# Blueberry_Pi.net
KiCad netlist of a schematic drawn in EAGLE
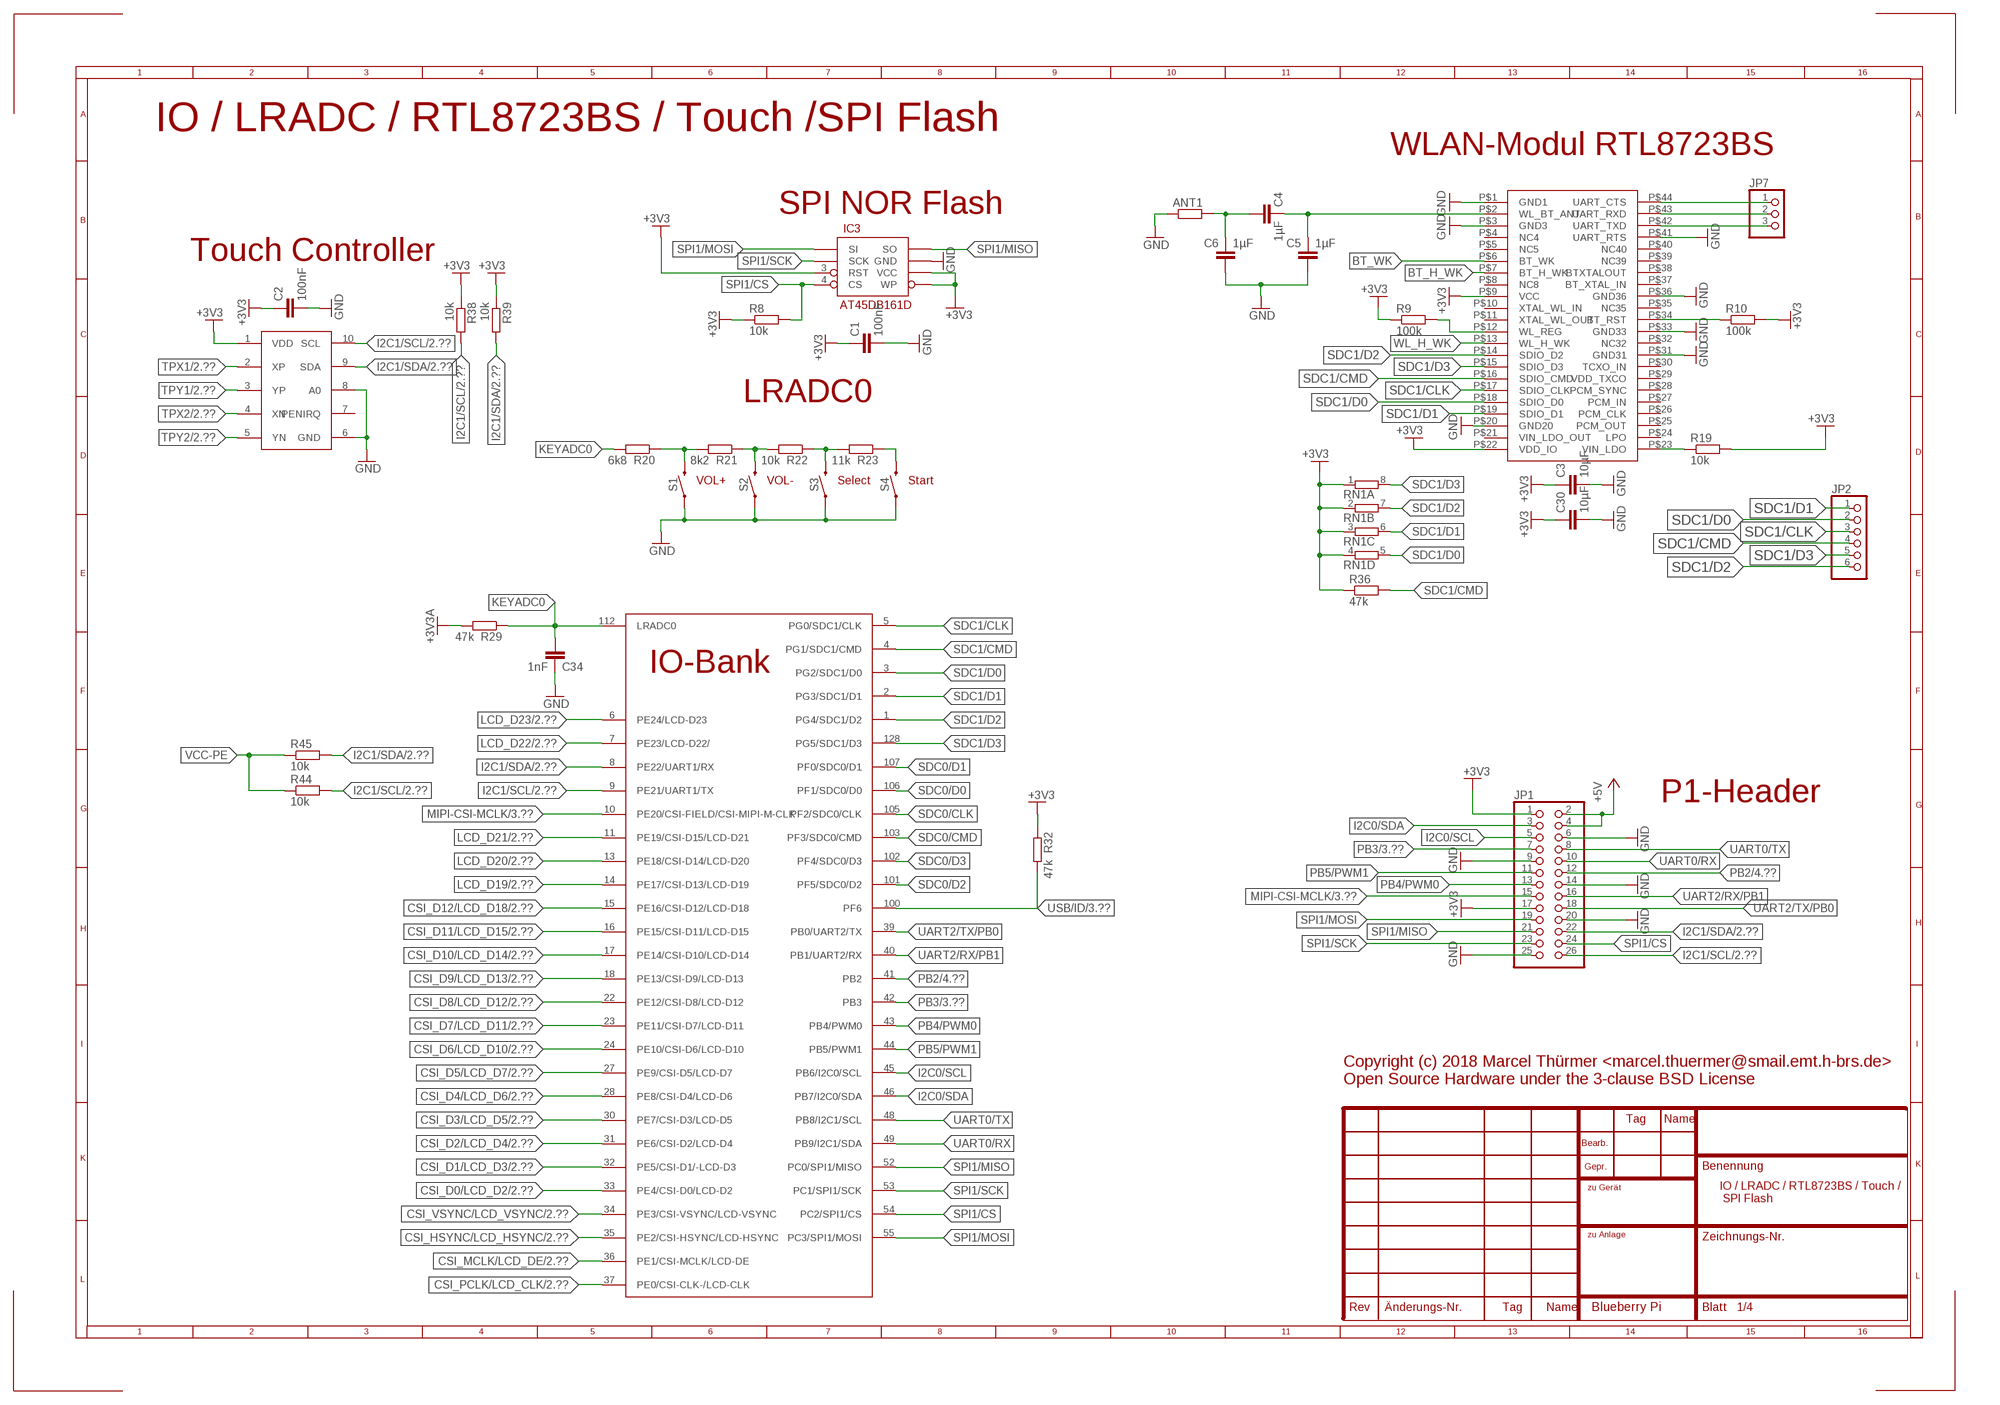
[diagram p0: schematic, sheet 1]
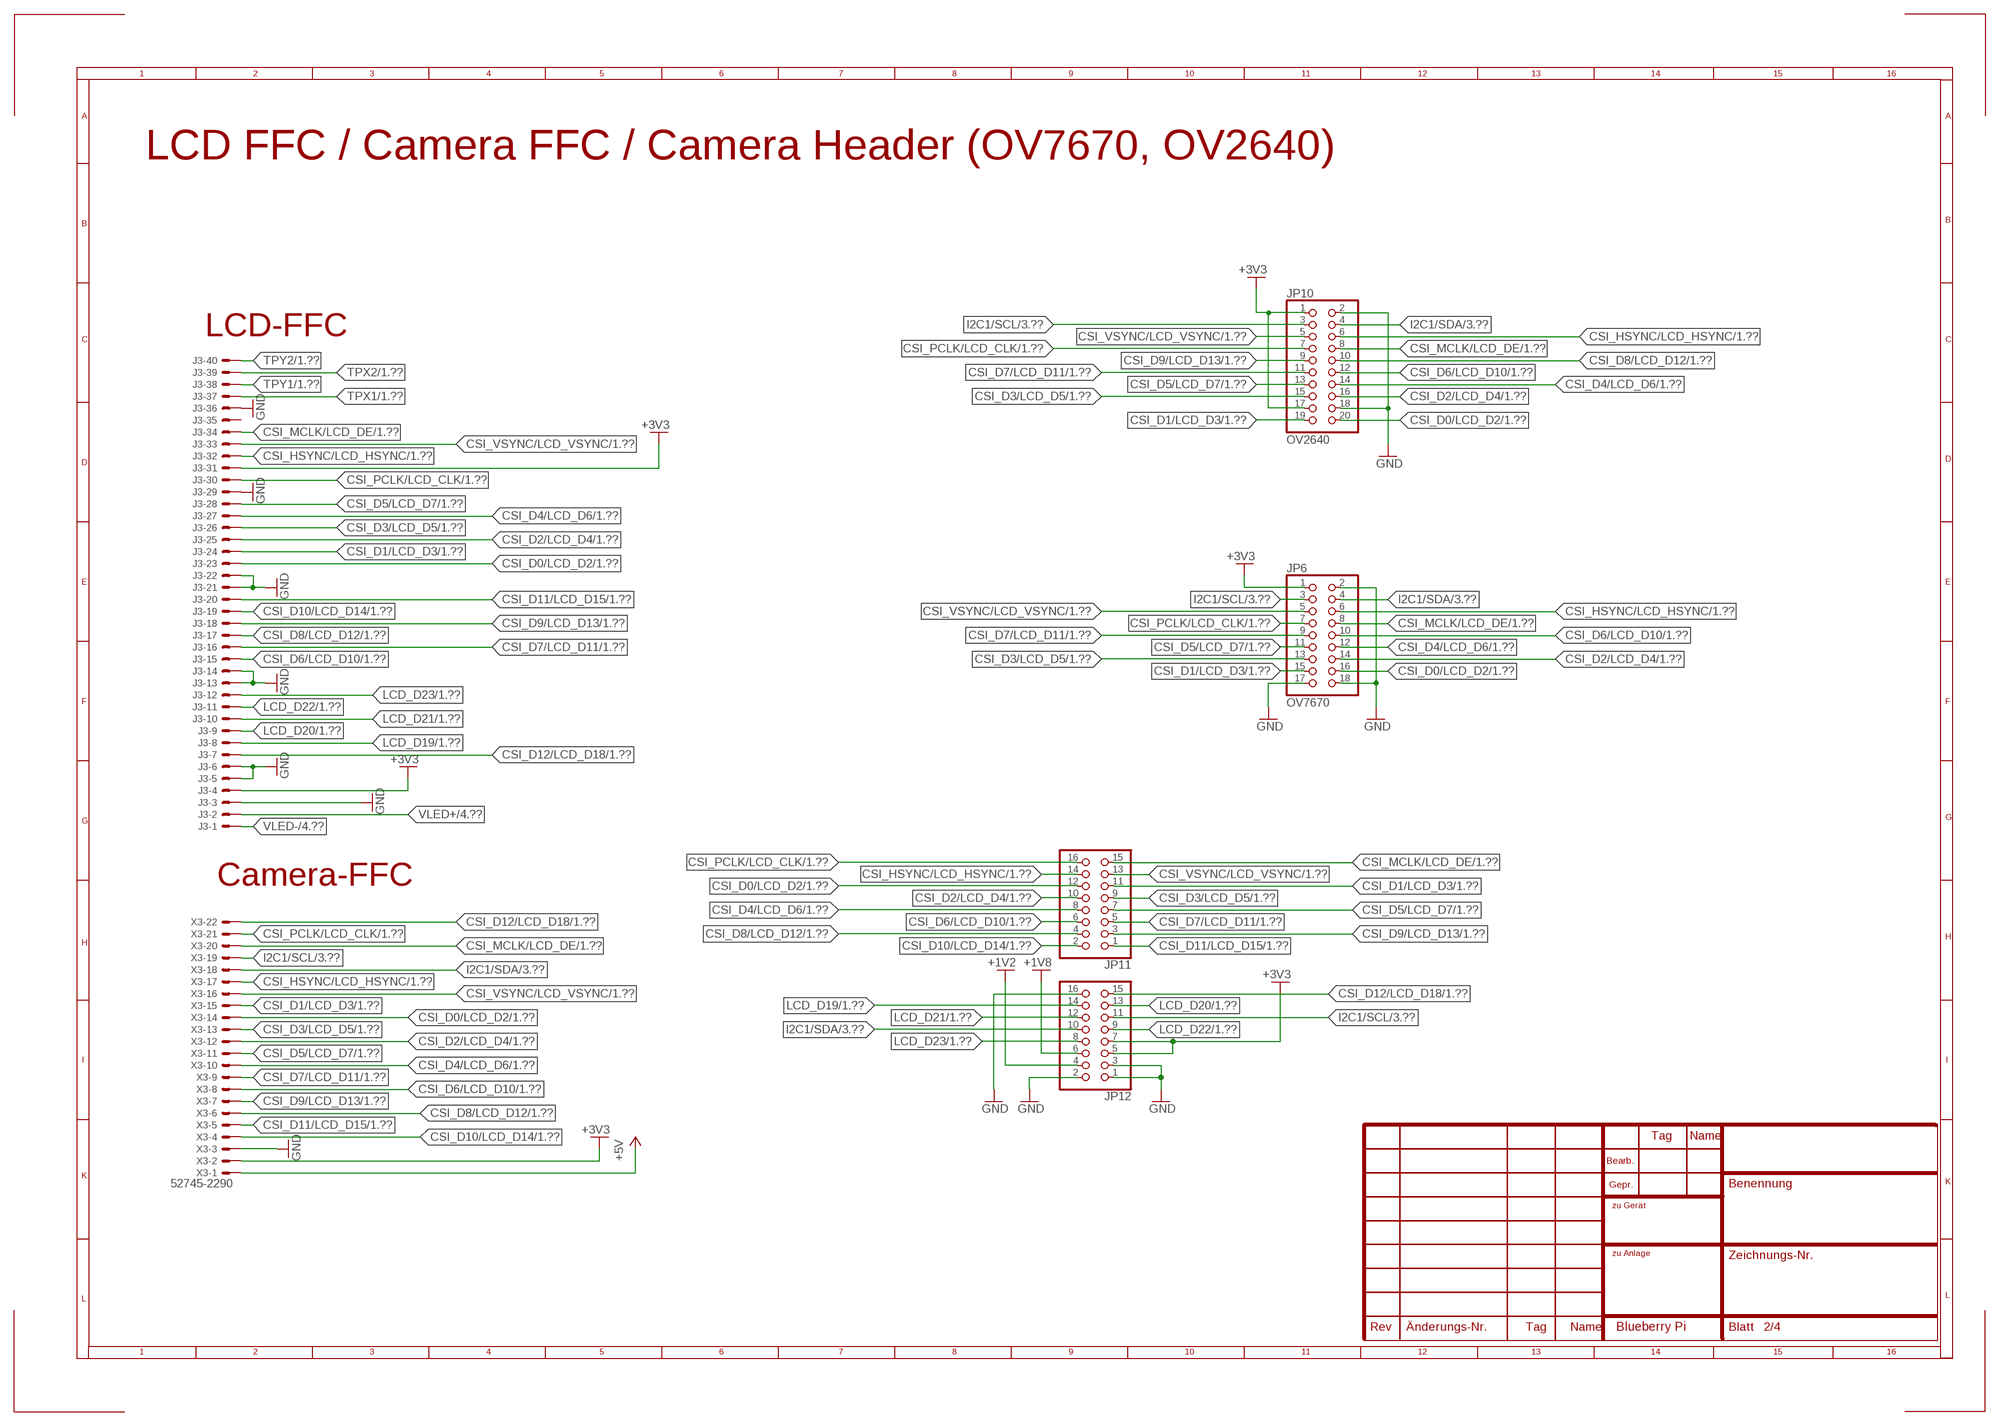
[diagram p1: schematic, sheet 2]
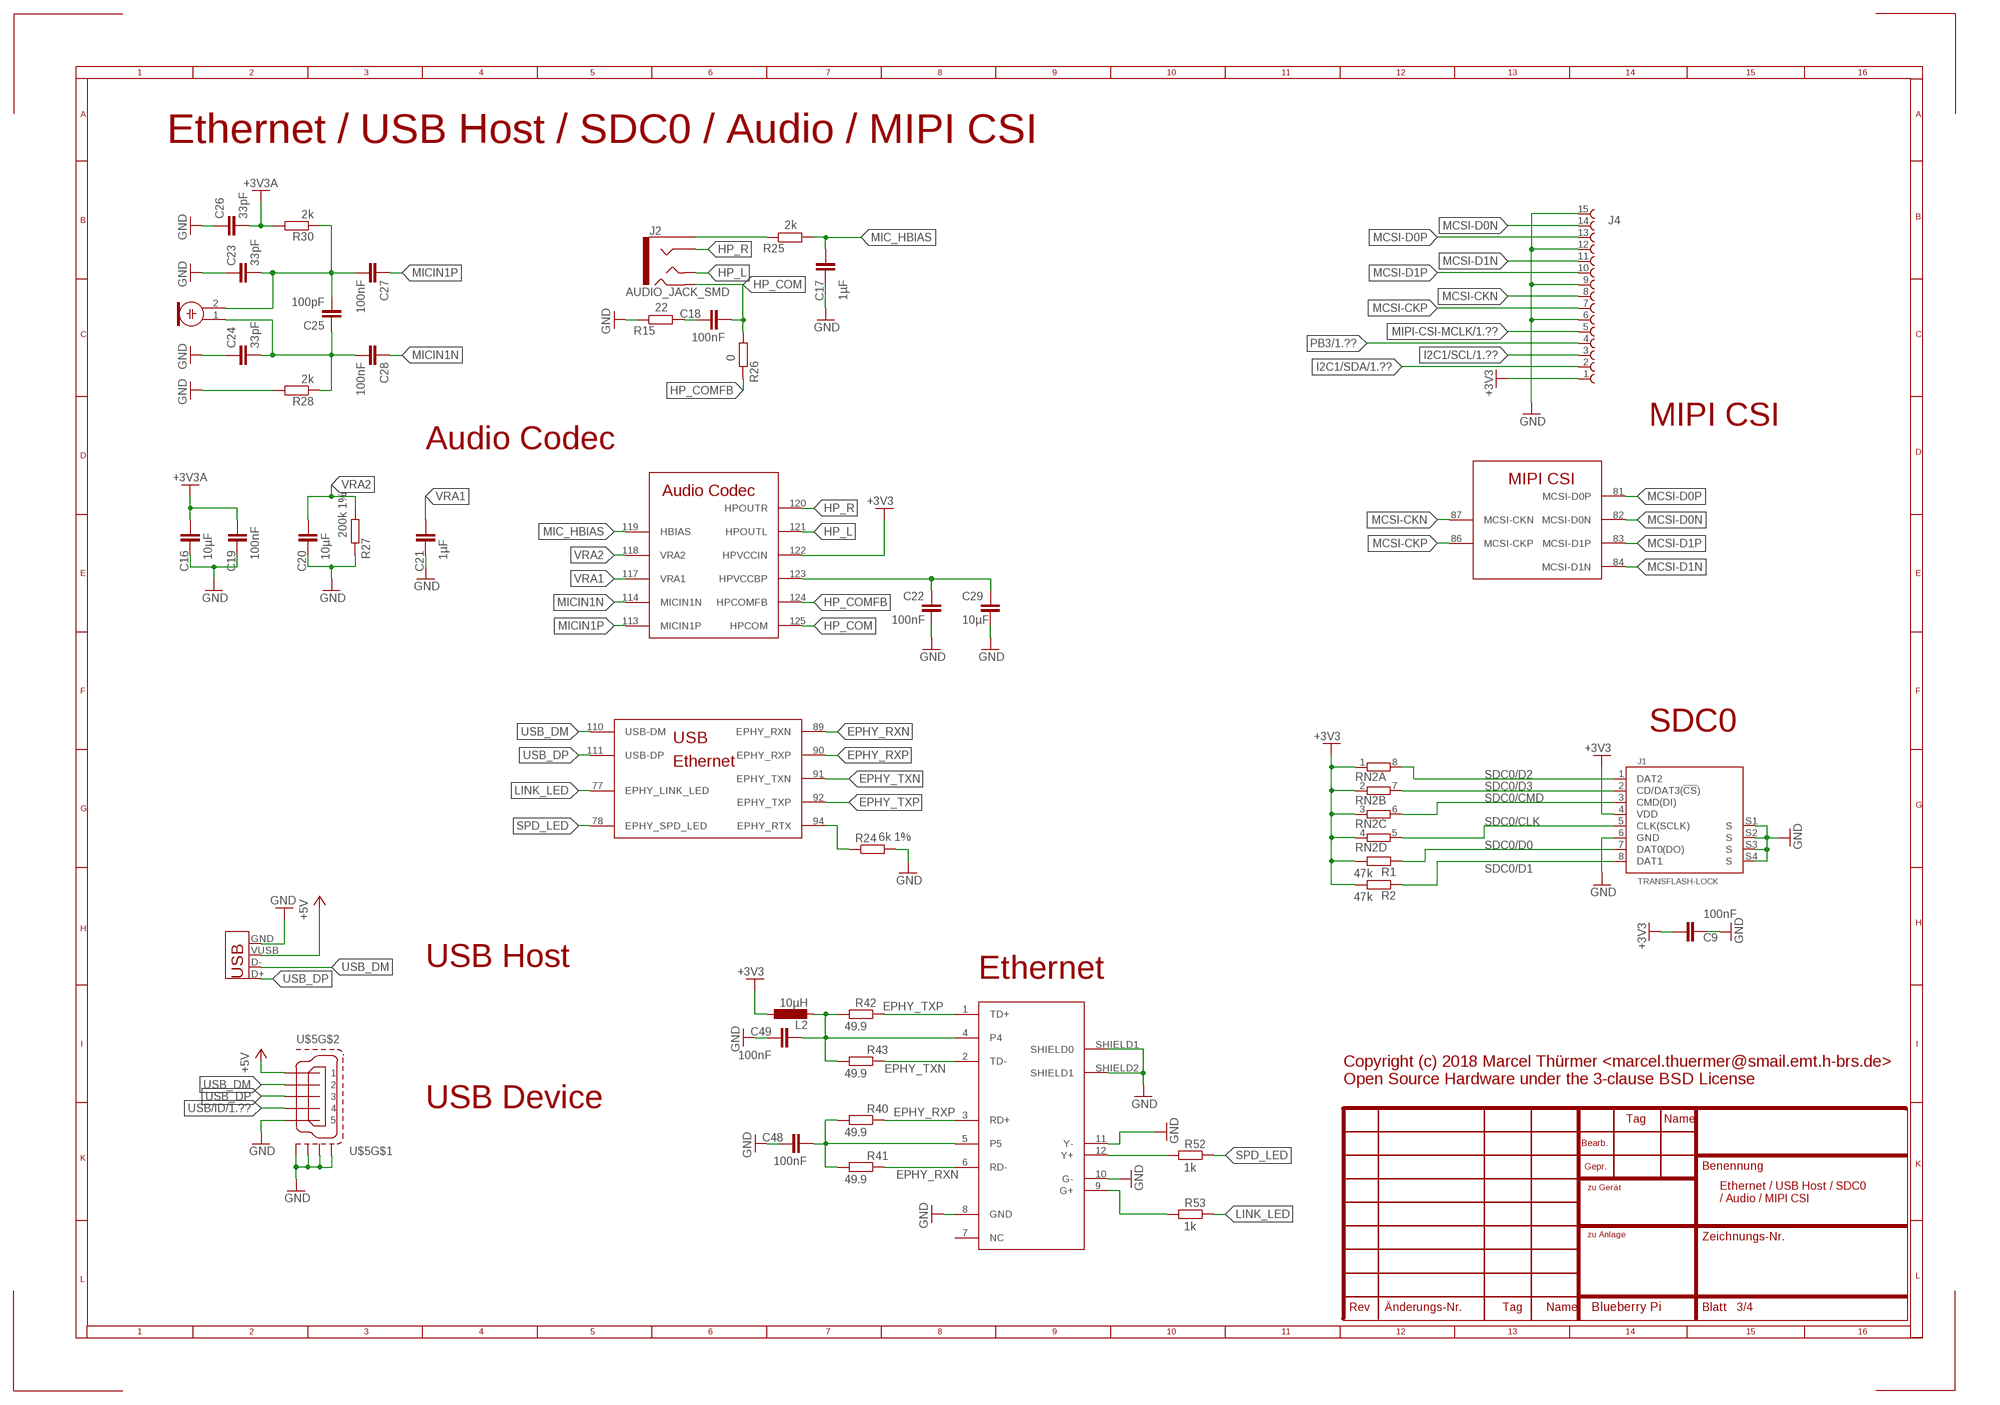
[diagram p2: schematic, sheet 3]
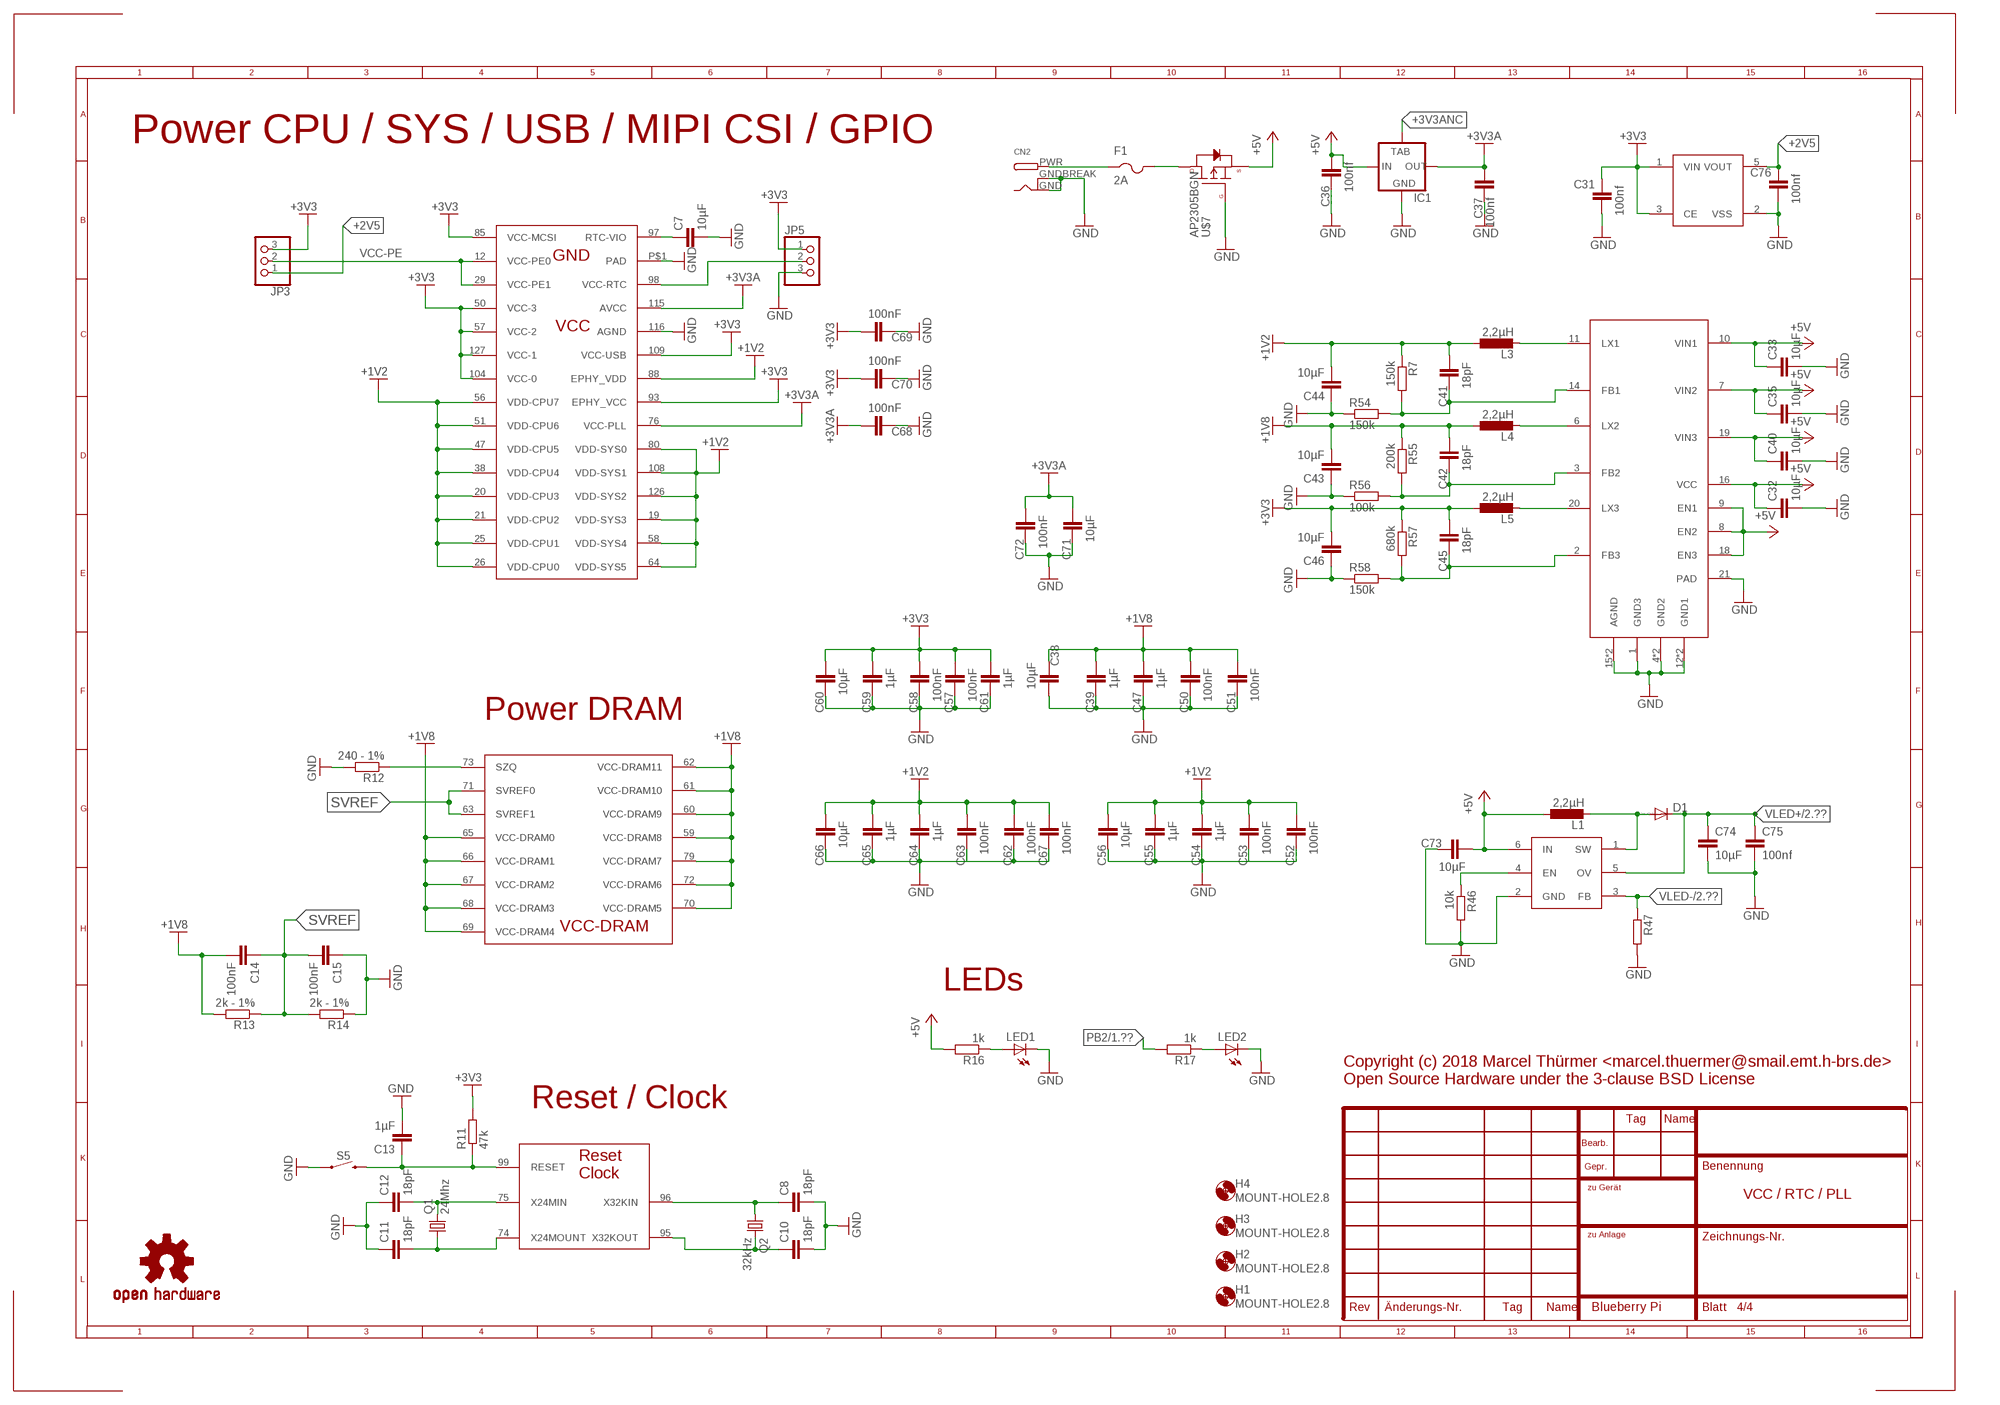
[diagram p3: schematic, sheet 4]

(export (version "E")
  (design (tool "Eeschema 10.0.6"))
  (components
    (comp (ref "J3")
      (value "40PINFPCH15-1LW")
      (footprint "eagle-import:XF2H-4015-1LW")
      (libsource (lib "eagle-import") (part "40PINFPC15-1LWH"))
    )
    (comp (ref "JP6")
      (value "OV7670")
      (footprint "eagle-import:2X09")
      (libsource (lib "eagle-import") (part "PINHD-2X9"))
    )
    (comp (ref "JP10")
      (value "OV2640")
      (footprint "eagle-import:2X10")
      (libsource (lib "eagle-import") (part "PINHD-2X10"))
    )
    (comp (ref "JP11")
      (value "PINHD-2X8M")
      (footprint "eagle-import:2X08M")
      (libsource (lib "eagle-import") (part "PINHD-2X8M"))
    )
    (comp (ref "JP12")
      (value "PINHD-2X8M")
      (footprint "eagle-import:2X08M")
      (libsource (lib "eagle-import") (part "PINHD-2X8M"))
    )
    (comp (ref "X3")
      (value "52745-2290")
      (footprint "eagle-import:52745-2290")
      (libsource (lib "eagle-import") (part "52745-2290"))
    )
    (comp (ref "ANT1")
      (value "R-EU_R1206")
      (footprint "eagle-import:R1206")
      (libsource (lib "eagle-import") (part "R-EU_R1206"))
    )
    (comp (ref "C1")
      (value "100nF")
      (footprint "eagle-import:C0603")
      (libsource (lib "eagle-import") (part "C-EUC0603"))
    )
    (comp (ref "C2")
      (value "100nF")
      (footprint "eagle-import:C0603")
      (libsource (lib "eagle-import") (part "C-EUC0603"))
    )
    (comp (ref "C3")
      (value "10µF")
      (footprint "eagle-import:C0805")
      (libsource (lib "eagle-import") (part "C-EUC0805"))
    )
    (comp (ref "C4")
      (value "1µF")
      (footprint "eagle-import:C0603")
      (libsource (lib "eagle-import") (part "C-EUC0603"))
    )
    (comp (ref "C5")
      (value "1µF")
      (footprint "eagle-import:C0603")
      (libsource (lib "eagle-import") (part "C-EUC0603"))
    )
    (comp (ref "C6")
      (value "1µF")
      (footprint "eagle-import:C0603")
      (libsource (lib "eagle-import") (part "C-EUC0603"))
    )
    (comp (ref "C30")
      (value "10µF")
      (footprint "eagle-import:C0805")
      (libsource (lib "eagle-import") (part "C-EUC0805"))
    )
    (comp (ref "C34")
      (value "1nF")
      (footprint "eagle-import:C0603")
      (libsource (lib "eagle-import") (part "C-EUC0603"))
    )
    (comp (ref "IC3")
      (value "AT45DB161D")
      (footprint "eagle-import:SO08-EIAJ")
      (libsource (lib "eagle-import") (part "AT45DB161D"))
    )
    (comp (ref "JP1")
      (value "PINHD-2X13")
      (footprint "eagle-import:2X13")
      (libsource (lib "eagle-import") (part "PINHD-2X13"))
    )
    (comp (ref "JP2")
      (value "PINHD-1X6_2.00")
      (footprint "eagle-import:1X06M")
      (libsource (lib "eagle-import") (part "PINHD-1X6_2.00"))
    )
    (comp (ref "JP7")
      (value "PINHD-1X3M")
      (footprint "eagle-import:1X03M")
      (libsource (lib "eagle-import") (part "PINHD-1X3M"))
    )
    (comp (ref "R8")
      (value "10k")
      (footprint "eagle-import:R0603")
      (libsource (lib "eagle-import") (part "R-EU_R0603"))
    )
    (comp (ref "R9")
      (value "100k")
      (footprint "eagle-import:R0603")
      (libsource (lib "eagle-import") (part "R-EU_R0603"))
    )
    (comp (ref "R10")
      (value "100k")
      (footprint "eagle-import:R0603")
      (libsource (lib "eagle-import") (part "R-EU_R0603"))
    )
    (comp (ref "R19")
      (value "10k")
      (footprint "eagle-import:R0603")
      (libsource (lib "eagle-import") (part "R-EU_R0603"))
    )
    (comp (ref "R20")
      (value "6k8")
      (footprint "eagle-import:R0603")
      (libsource (lib "eagle-import") (part "R-EU_R0603"))
    )
    (comp (ref "R21")
      (value "8k2")
      (footprint "eagle-import:R0603")
      (libsource (lib "eagle-import") (part "R-EU_R0603"))
    )
    (comp (ref "R22")
      (value "10k")
      (footprint "eagle-import:R0603")
      (libsource (lib "eagle-import") (part "R-EU_R0603"))
    )
    (comp (ref "R23")
      (value "11k")
      (footprint "eagle-import:R0603")
      (libsource (lib "eagle-import") (part "R-EU_R0603"))
    )
    (comp (ref "R29")
      (value "47k")
      (footprint "eagle-import:R0603")
      (libsource (lib "eagle-import") (part "R-EU_R0603"))
    )
    (comp (ref "R32")
      (value "47k")
      (footprint "eagle-import:R0603")
      (libsource (lib "eagle-import") (part "R-EU_R0603"))
    )
    (comp (ref "R36")
      (value "47k")
      (footprint "eagle-import:R0603")
      (libsource (lib "eagle-import") (part "R-EU_R0603"))
    )
    (comp (ref "R38")
      (value "10k")
      (footprint "eagle-import:R0603")
      (libsource (lib "eagle-import") (part "R-EU_R0603"))
    )
    (comp (ref "R39")
      (value "10k")
      (footprint "eagle-import:R0603")
      (libsource (lib "eagle-import") (part "R-EU_R0603"))
    )
    (comp (ref "R44")
      (value "10k")
      (footprint "eagle-import:R0603")
      (libsource (lib "eagle-import") (part "R-EU_R0603"))
    )
    (comp (ref "R45")
      (value "10k")
      (footprint "eagle-import:R0603")
      (libsource (lib "eagle-import") (part "R-EU_R0603"))
    )
    (comp (ref "RN1")
      (value "4R-NEXB38V")
      (footprint "eagle-import:EXB38V")
      (libsource (lib "eagle-import") (part "4R-NEXB38V"))
    )
    (comp (ref "S1")
      (value "MOMENTARY-SWITCH-SPST-SMD-6.0X3.5MM")
      (footprint "eagle-import:TACTILE_SWITCH_SMD_6.0X3.5MM")
      (libsource (lib "eagle-import") (part "MOMENTARY-SWITCH-SPST-SMD-6.0X3.5MM"))
    )
    (comp (ref "S2")
      (value "MOMENTARY-SWITCH-SPST-SMD-6.0X3.5MM")
      (footprint "eagle-import:TACTILE_SWITCH_SMD_6.0X3.5MM")
      (libsource (lib "eagle-import") (part "MOMENTARY-SWITCH-SPST-SMD-6.0X3.5MM"))
    )
    (comp (ref "S3")
      (value "MOMENTARY-SWITCH-SPST-SMD-6.0X3.5MM")
      (footprint "eagle-import:TACTILE_SWITCH_SMD_6.0X3.5MM")
      (libsource (lib "eagle-import") (part "MOMENTARY-SWITCH-SPST-SMD-6.0X3.5MM"))
    )
    (comp (ref "S4")
      (value "MOMENTARY-SWITCH-SPST-SMD-6.0X3.5MM")
      (footprint "eagle-import:TACTILE_SWITCH_SMD_6.0X3.5MM")
      (libsource (lib "eagle-import") (part "MOMENTARY-SWITCH-SPST-SMD-6.0X3.5MM"))
    )
    (comp (ref "U$1")
      (value "V3S")
      (footprint "eagle-import:QFP-128")
      (libsource (lib "eagle-import") (part "V3S"))
    )
    (comp (ref "U$2")
      (value "RTL8723BS")
      (footprint "eagle-import:LGA")
      (libsource (lib "eagle-import") (part "RTL8723BS"))
    )
    (comp (ref "U$8")
      (value "NS2009")
      (footprint "eagle-import:MSOP10")
      (libsource (lib "eagle-import") (part "NS2009"))
    )
    (comp (ref "C7")
      (value "10µF")
      (footprint "eagle-import:C0805")
      (libsource (lib "eagle-import") (part "C-EUC0805"))
    )
    (comp (ref "C8")
      (value "18pF")
      (footprint "eagle-import:C0603")
      (libsource (lib "eagle-import") (part "C-EUC0603"))
    )
    (comp (ref "C10")
      (value "18pF")
      (footprint "eagle-import:C0603")
      (libsource (lib "eagle-import") (part "C-EUC0603"))
    )
    (comp (ref "C11")
      (value "18pF")
      (footprint "eagle-import:C0603")
      (libsource (lib "eagle-import") (part "C-EUC0603"))
    )
    (comp (ref "C12")
      (value "18pF")
      (footprint "eagle-import:C0603")
      (libsource (lib "eagle-import") (part "C-EUC0603"))
    )
    (comp (ref "C13")
      (value "1µF")
      (footprint "eagle-import:C0603")
      (libsource (lib "eagle-import") (part "C-EUC0603"))
    )
    (comp (ref "C14")
      (value "100nF")
      (footprint "eagle-import:C0603")
      (libsource (lib "eagle-import") (part "C-EUC0603"))
    )
    (comp (ref "C15")
      (value "100nF")
      (footprint "eagle-import:C0603")
      (libsource (lib "eagle-import") (part "C-EUC0603"))
    )
    (comp (ref "C31")
      (value "100nf")
      (footprint "eagle-import:C0603")
      (libsource (lib "eagle-import") (part "C-EUC0603"))
    )
    (comp (ref "C32")
      (value "10µF")
      (footprint "eagle-import:C0805")
      (libsource (lib "eagle-import") (part "rcl_334_C-EUC0805"))
    )
    (comp (ref "C33")
      (value "10µF")
      (footprint "eagle-import:C0805")
      (libsource (lib "eagle-import") (part "rcl_334_C-EUC0805"))
    )
    (comp (ref "C35")
      (value "10µF")
      (footprint "eagle-import:C0805")
      (libsource (lib "eagle-import") (part "rcl_334_C-EUC0805"))
    )
    (comp (ref "C36")
      (value "100nf")
      (footprint "eagle-import:C0603")
      (libsource (lib "eagle-import") (part "C-EUC0603"))
    )
    (comp (ref "C37")
      (value "100nf")
      (footprint "eagle-import:C0603")
      (libsource (lib "eagle-import") (part "C-EUC0603"))
    )
    (comp (ref "C38")
      (value "10µF")
      (footprint "eagle-import:C0603")
      (libsource (lib "eagle-import") (part "C-EUC0603"))
    )
    (comp (ref "C39")
      (value "1µF")
      (footprint "eagle-import:C0603")
      (libsource (lib "eagle-import") (part "C-EUC0603"))
    )
    (comp (ref "C40")
      (value "10µF")
      (footprint "eagle-import:C0805")
      (libsource (lib "eagle-import") (part "rcl_334_C-EUC0805"))
    )
    (comp (ref "C41")
      (value "18pF")
      (footprint "eagle-import:C0603")
      (libsource (lib "eagle-import") (part "C-EUC0603"))
    )
    (comp (ref "C42")
      (value "18pF")
      (footprint "eagle-import:C0603")
      (libsource (lib "eagle-import") (part "C-EUC0603"))
    )
    (comp (ref "C43")
      (value "10µF")
      (footprint "eagle-import:C0805")
      (libsource (lib "eagle-import") (part "rcl_334_C-EUC0805"))
    )
    (comp (ref "C44")
      (value "10µF")
      (footprint "eagle-import:C0805")
      (libsource (lib "eagle-import") (part "rcl_334_C-EUC0805"))
    )
    (comp (ref "C45")
      (value "18pF")
      (footprint "eagle-import:C0603")
      (libsource (lib "eagle-import") (part "C-EUC0603"))
    )
    (comp (ref "C46")
      (value "10µF")
      (footprint "eagle-import:C0805")
      (libsource (lib "eagle-import") (part "rcl_334_C-EUC0805"))
    )
    (comp (ref "C47")
      (value "1µF")
      (footprint "eagle-import:C0603")
      (libsource (lib "eagle-import") (part "C-EUC0603"))
    )
    (comp (ref "C50")
      (value "100nF")
      (footprint "eagle-import:C0805")
      (libsource (lib "eagle-import") (part "C-EUC0805"))
    )
    (comp (ref "C51")
      (value "100nF")
      (footprint "eagle-import:C0603")
      (libsource (lib "eagle-import") (part "C-EUC0603"))
    )
    (comp (ref "C52")
      (value "100nF")
      (footprint "eagle-import:C0805")
      (libsource (lib "eagle-import") (part "C-EUC0805"))
    )
    (comp (ref "C53")
      (value "100nF")
      (footprint "eagle-import:C0603")
      (libsource (lib "eagle-import") (part "C-EUC0603"))
    )
    (comp (ref "C54")
      (value "1µF")
      (footprint "eagle-import:C0805")
      (libsource (lib "eagle-import") (part "C-EUC0805"))
    )
    (comp (ref "C55")
      (value "1µF")
      (footprint "eagle-import:C0603")
      (libsource (lib "eagle-import") (part "C-EUC0603"))
    )
    (comp (ref "C56")
      (value "10µF")
      (footprint "eagle-import:C0603")
      (libsource (lib "eagle-import") (part "C-EUC0603"))
    )
    (comp (ref "C57")
      (value "100nF")
      (footprint "eagle-import:C0603")
      (libsource (lib "eagle-import") (part "C-EUC0603"))
    )
    (comp (ref "C58")
      (value "100nF")
      (footprint "eagle-import:C0603")
      (libsource (lib "eagle-import") (part "C-EUC0603"))
    )
    (comp (ref "C59")
      (value "1µF")
      (footprint "eagle-import:C0805")
      (libsource (lib "eagle-import") (part "C-EUC0805"))
    )
    (comp (ref "C60")
      (value "10µF")
      (footprint "eagle-import:C0603")
      (libsource (lib "eagle-import") (part "C-EUC0603"))
    )
    (comp (ref "C61")
      (value "1µF")
      (footprint "eagle-import:C0805")
      (libsource (lib "eagle-import") (part "C-EUC0805"))
    )
    (comp (ref "C62")
      (value "100nF")
      (footprint "eagle-import:C0603")
      (libsource (lib "eagle-import") (part "C-EUC0603"))
    )
    (comp (ref "C63")
      (value "100nF")
      (footprint "eagle-import:C0805")
      (libsource (lib "eagle-import") (part "C-EUC0805"))
    )
    (comp (ref "C64")
      (value "1µF")
      (footprint "eagle-import:C0603")
      (libsource (lib "eagle-import") (part "C-EUC0603"))
    )
    (comp (ref "C65")
      (value "1µF")
      (footprint "eagle-import:C0603")
      (libsource (lib "eagle-import") (part "C-EUC0603"))
    )
    (comp (ref "C66")
      (value "10µF")
      (footprint "eagle-import:C0805")
      (libsource (lib "eagle-import") (part "C-EUC0805"))
    )
    (comp (ref "C67")
      (value "100nF")
      (footprint "eagle-import:C0603")
      (libsource (lib "eagle-import") (part "C-EUC0603"))
    )
    (comp (ref "C68")
      (value "100nF")
      (footprint "eagle-import:C0603")
      (libsource (lib "eagle-import") (part "C-EUC0603"))
    )
    (comp (ref "C69")
      (value "100nF")
      (footprint "eagle-import:C0805")
      (libsource (lib "eagle-import") (part "C-EUC0805"))
    )
    (comp (ref "C70")
      (value "100nF")
      (footprint "eagle-import:C0603")
      (libsource (lib "eagle-import") (part "C-EUC0603"))
    )
    (comp (ref "C71")
      (value "10µF")
      (footprint "eagle-import:C0603")
      (libsource (lib "eagle-import") (part "C-EUC0603"))
    )
    (comp (ref "C72")
      (value "100nF")
      (footprint "eagle-import:C0603")
      (libsource (lib "eagle-import") (part "C-EUC0603"))
    )
    (comp (ref "C73")
      (value "10µF")
      (footprint "eagle-import:C0805")
      (libsource (lib "eagle-import") (part "C-EUC0805"))
    )
    (comp (ref "C74")
      (value "10µF")
      (footprint "eagle-import:C0805")
      (libsource (lib "eagle-import") (part "C-EUC0805"))
    )
    (comp (ref "C75")
      (value "100nf")
      (footprint "eagle-import:C0603")
      (libsource (lib "eagle-import") (part "C-EUC0603"))
    )
    (comp (ref "C76")
      (value "100nf")
      (footprint "eagle-import:C0603")
      (libsource (lib "eagle-import") (part "C-EUC0603"))
    )
    (comp (ref "CN2")
      (value "DCBARRELPTH")
      (footprint "eagle-import:DCJACK_2MM_PTH")
      (libsource (lib "eagle-import") (part "DCBARRELPTH"))
    )
    (comp (ref "D1")
      (value "DIODE-SOD323-W")
      (footprint "eagle-import:SOD323-W")
      (libsource (lib "eagle-import") (part "DIODE-SOD323-W"))
    )
    (comp (ref "F1")
      (value "2A")
      (footprint "eagle-import:R1206")
      (libsource (lib "eagle-import") (part "PTCFUSE-1206"))
    )
    (comp (ref "H1")
      (value "MOUNT-HOLE2.8")
      (footprint "eagle-import:2,8")
      (libsource (lib "eagle-import") (part "MOUNT-HOLE2.8"))
    )
    (comp (ref "H2")
      (value "MOUNT-HOLE2.8")
      (footprint "eagle-import:2,8")
      (libsource (lib "eagle-import") (part "MOUNT-HOLE2.8"))
    )
    (comp (ref "H3")
      (value "MOUNT-HOLE2.8")
      (footprint "eagle-import:2,8")
      (libsource (lib "eagle-import") (part "holes_237_MOUNT-HOLE2.8"))
    )
    (comp (ref "H4")
      (value "MOUNT-HOLE2.8")
      (footprint "eagle-import:2,8")
      (libsource (lib "eagle-import") (part "MOUNT-HOLE2.8"))
    )
    (comp (ref "IC1")
      (value "LM1117")
      (footprint "eagle-import:SOT223")
      (libsource (lib "eagle-import") (part "LM1117"))
    )
    (comp (ref "JP3")
      (value "PINHD-1X3")
      (footprint "eagle-import:1X03")
      (libsource (lib "eagle-import") (part "PINHD-1X3"))
    )
    (comp (ref "JP5")
      (value "PINHD-1X3")
      (footprint "eagle-import:1X03")
      (libsource (lib "eagle-import") (part "PINHD-1X3"))
    )
    (comp (ref "L1")
      (value "2,2µH")
      (footprint "eagle-import:ODD-INDUCTOR")
      (libsource (lib "eagle-import") (part "L-EU"))
    )
    (comp (ref "L3")
      (value "2,2µH")
      (footprint "eagle-import:ODD-INDUCTOR")
      (libsource (lib "eagle-import") (part "L-EU"))
    )
    (comp (ref "L4")
      (value "2,2µH")
      (footprint "eagle-import:ODD-INDUCTOR")
      (libsource (lib "eagle-import") (part "L-EU"))
    )
    (comp (ref "L5")
      (value "2,2µH")
      (footprint "eagle-import:ODD-INDUCTOR")
      (libsource (lib "eagle-import") (part "L-EU"))
    )
    (comp (ref "LED1")
      (value "LEDCHIPLED_0805")
      (footprint "eagle-import:CHIPLED_0805")
      (libsource (lib "eagle-import") (part "LEDCHIPLED_0805"))
    )
    (comp (ref "LED2")
      (value "LEDCHIPLED_0805")
      (footprint "eagle-import:CHIPLED_0805")
      (libsource (lib "eagle-import") (part "LEDCHIPLED_0805"))
    )
    (comp (ref "LOGO2")
      (value "OSHW-LOGOL")
      (footprint "eagle-import:OSHW-LOGO-L")
      (libsource (lib "eagle-import") (part "OSHW-LOGOL"))
    )
    (comp (ref "Q1")
      (value "24Mhz")
      (footprint "eagle-import:HC49U-V")
      (libsource (lib "eagle-import") (part "CRYSTALHC49U-V"))
    )
    (comp (ref "Q2")
      (value "32kHz")
      (footprint "eagle-import:TC38H")
      (libsource (lib "eagle-import") (part "CRYSTALTC38H"))
    )
    (comp (ref "R7")
      (value "150k")
      (footprint "eagle-import:R0603")
      (libsource (lib "eagle-import") (part "R-EU_R0603"))
    )
    (comp (ref "R11")
      (value "47k")
      (footprint "eagle-import:R0603")
      (libsource (lib "eagle-import") (part "R-EU_R0603"))
    )
    (comp (ref "R12")
      (value "240 - 1%")
      (footprint "eagle-import:R0603")
      (libsource (lib "eagle-import") (part "R-EU_R0603"))
    )
    (comp (ref "R13")
      (value "2k - 1%")
      (footprint "eagle-import:R0603")
      (libsource (lib "eagle-import") (part "R-EU_R0603"))
    )
    (comp (ref "R14")
      (value "2k - 1%")
      (footprint "eagle-import:R0603")
      (libsource (lib "eagle-import") (part "R-EU_R0603"))
    )
    (comp (ref "R16")
      (value "1k")
      (footprint "eagle-import:R0603")
      (libsource (lib "eagle-import") (part "R-EU_R0603"))
    )
    (comp (ref "R17")
      (value "1k")
      (footprint "eagle-import:R0603")
      (libsource (lib "eagle-import") (part "R-EU_R0603"))
    )
    (comp (ref "R46")
      (value "10k")
      (footprint "eagle-import:R0603")
      (libsource (lib "eagle-import") (part "R-EU_R0603"))
    )
    (comp (ref "R47")
      (value "R-EU_R0603")
      (footprint "eagle-import:R0603")
      (libsource (lib "eagle-import") (part "R-EU_R0603"))
    )
    (comp (ref "R54")
      (value "150k")
      (footprint "eagle-import:R0603")
      (libsource (lib "eagle-import") (part "R-EU_R0603"))
    )
    (comp (ref "R55")
      (value "200k")
      (footprint "eagle-import:R0603")
      (libsource (lib "eagle-import") (part "R-EU_R0603"))
    )
    (comp (ref "R56")
      (value "100k")
      (footprint "eagle-import:R0603")
      (libsource (lib "eagle-import") (part "R-EU_R0603"))
    )
    (comp (ref "R57")
      (value "680k")
      (footprint "eagle-import:R0603")
      (libsource (lib "eagle-import") (part "R-EU_R0603"))
    )
    (comp (ref "R58")
      (value "150k")
      (footprint "eagle-import:R0603")
      (libsource (lib "eagle-import") (part "R-EU_R0603"))
    )
    (comp (ref "S5")
      (value "MOMENTARY-SWITCH-SPST-SMD-6.0X3.5MM")
      (footprint "eagle-import:TACTILE_SWITCH_SMD_6.0X3.5MM")
      (libsource (lib "eagle-import") (part "MOMENTARY-SWITCH-SPST-SMD-6.0X3.5MM"))
    )
    (comp (ref "U$4")
      (value "EA3036")
      (footprint "eagle-import:QFN20")
      (libsource (lib "eagle-import") (part "EA3036"))
    )
    (comp (ref "U$6")
      (value "XC6204")
      (footprint "eagle-import:SOT25")
      (libsource (lib "eagle-import") (part "XC6204XC6204"))
    )
    (comp (ref "U$7")
      (value "AP2305BGN")
      (footprint "eagle-import:SOT23-3")
      (libsource (lib "eagle-import") (part "P-CHANNEL-MOSFET"))
    )
    (comp (ref "U$9")
      (value "PT4101")
      (footprint "eagle-import:SOT23-6")
      (libsource (lib "eagle-import") (part "PT4101"))
    )
    (comp (ref "C9")
      (value "100nF")
      (footprint "eagle-import:C0603")
      (libsource (lib "eagle-import") (part "C-EUC0603"))
    )
    (comp (ref "C16")
      (value "10µF")
      (footprint "eagle-import:C0805")
      (libsource (lib "eagle-import") (part "C-EUC0805"))
    )
    (comp (ref "C17")
      (value "1µF")
      (footprint "eagle-import:C0603")
      (libsource (lib "eagle-import") (part "C-EUC0603"))
    )
    (comp (ref "C18")
      (value "100nF")
      (footprint "eagle-import:C0603")
      (libsource (lib "eagle-import") (part "C-EUC0603"))
    )
    (comp (ref "C19")
      (value "100nF")
      (footprint "eagle-import:C0603")
      (libsource (lib "eagle-import") (part "C-EUC0603"))
    )
    (comp (ref "C20")
      (value "10µF")
      (footprint "eagle-import:C0805")
      (libsource (lib "eagle-import") (part "C-EUC0805"))
    )
    (comp (ref "C21")
      (value "1µF")
      (footprint "eagle-import:C0603")
      (libsource (lib "eagle-import") (part "C-EUC0603"))
    )
    (comp (ref "C22")
      (value "100nF")
      (footprint "eagle-import:C0603")
      (libsource (lib "eagle-import") (part "C-EUC0603"))
    )
    (comp (ref "C23")
      (value "33pF")
      (footprint "eagle-import:C0603")
      (libsource (lib "eagle-import") (part "C-EUC0603"))
    )
    (comp (ref "C24")
      (value "33pF")
      (footprint "eagle-import:C0603")
      (libsource (lib "eagle-import") (part "C-EUC0603"))
    )
    (comp (ref "C25")
      (value "100pF")
      (footprint "eagle-import:C0603")
      (libsource (lib "eagle-import") (part "C-EUC0603"))
    )
    (comp (ref "C26")
      (value "33pF")
      (footprint "eagle-import:C0603")
      (libsource (lib "eagle-import") (part "C-EUC0603"))
    )
    (comp (ref "C27")
      (value "100nF")
      (footprint "eagle-import:C0603")
      (libsource (lib "eagle-import") (part "C-EUC0603"))
    )
    (comp (ref "C28")
      (value "100nF")
      (footprint "eagle-import:C0603")
      (libsource (lib "eagle-import") (part "C-EUC0603"))
    )
    (comp (ref "C29")
      (value "10µF")
      (footprint "eagle-import:C0805")
      (libsource (lib "eagle-import") (part "C-EUC0805"))
    )
    (comp (ref "C48")
      (value "100nF")
      (footprint "eagle-import:C0603")
      (libsource (lib "eagle-import") (part "C-EUC0603"))
    )
    (comp (ref "C49")
      (value "100nF")
      (footprint "eagle-import:C0603")
      (libsource (lib "eagle-import") (part "C-EUC0603"))
    )
    (comp (ref "J1")
      (value "TRANSFLASH-LOCK")
      (footprint "eagle-import:TRANSFLASH-LOCK-SOCK")
      (libsource (lib "eagle-import") (part "TRANSFLASH-LOCK"))
    )
    (comp (ref "J2")
      (value "AUDIO_JACK_SMD")
      (footprint "eagle-import:AUDIO_JACK_3.5MM_TRRS_SMD_RA")
      (libsource (lib "eagle-import") (part "AUDIO_JACK_TRRSSMD_RA"))
    )
    (comp (ref "J4")
      (value "68611514122")
      (footprint "eagle-import:68611514122")
      (libsource (lib "eagle-import") (part "68611514122"))
    )
    (comp (ref "L2")
      (value "10µH")
      (footprint "eagle-import:L0805")
      (libsource (lib "eagle-import") (part "L-EUL0805"))
    )
    (comp (ref "MIC")
      (value "ELECTRET_MICROPHON-F6035AP")
      (footprint "eagle-import:F6035AP")
      (libsource (lib "eagle-import") (part "ELECTRET_MICROPHON-F6035AP"))
    )
    (comp (ref "R1")
      (value "47k")
      (footprint "eagle-import:R0603")
      (libsource (lib "eagle-import") (part "R-EU_R0603"))
    )
    (comp (ref "R2")
      (value "47k")
      (footprint "eagle-import:R0603")
      (libsource (lib "eagle-import") (part "R-EU_R0603"))
    )
    (comp (ref "R15")
      (value "22")
      (footprint "eagle-import:R0603")
      (libsource (lib "eagle-import") (part "R-EU_R0603"))
    )
    (comp (ref "R24")
      (value "6k 1%")
      (footprint "eagle-import:R0603")
      (libsource (lib "eagle-import") (part "R-EU_R0603"))
    )
    (comp (ref "R25")
      (value "2k")
      (footprint "eagle-import:R0603")
      (libsource (lib "eagle-import") (part "R-EU_R0603"))
    )
    (comp (ref "R26")
      (value "0")
      (footprint "eagle-import:R0603")
      (libsource (lib "eagle-import") (part "R-EU_R0603"))
    )
    (comp (ref "R27")
      (value "200k 1%")
      (footprint "eagle-import:R0603")
      (libsource (lib "eagle-import") (part "R-EU_R0603"))
    )
    (comp (ref "R28")
      (value "2k")
      (footprint "eagle-import:R0603")
      (libsource (lib "eagle-import") (part "R-EU_R0603"))
    )
    (comp (ref "R30")
      (value "2k")
      (footprint "eagle-import:R0603")
      (libsource (lib "eagle-import") (part "R-EU_R0603"))
    )
    (comp (ref "R40")
      (value "49.9")
      (footprint "eagle-import:R0603")
      (libsource (lib "eagle-import") (part "R-EU_R0603"))
    )
    (comp (ref "R41")
      (value "49.9")
      (footprint "eagle-import:R0603")
      (libsource (lib "eagle-import") (part "R-EU_R0603"))
    )
    (comp (ref "R42")
      (value "49.9")
      (footprint "eagle-import:R0603")
      (libsource (lib "eagle-import") (part "R-EU_R0603"))
    )
    (comp (ref "R43")
      (value "49.9")
      (footprint "eagle-import:R0603")
      (libsource (lib "eagle-import") (part "R-EU_R0603"))
    )
    (comp (ref "R52")
      (value "1k")
      (footprint "eagle-import:R0603")
      (libsource (lib "eagle-import") (part "R-EU_R0603"))
    )
    (comp (ref "R53")
      (value "1k")
      (footprint "eagle-import:R0603")
      (libsource (lib "eagle-import") (part "R-EU_R0603"))
    )
    (comp (ref "RN2")
      (value "4R-NEXB38V")
      (footprint "eagle-import:EXB38V")
      (libsource (lib "eagle-import") (part "4R-NEXB38V"))
    )
    (comp (ref "U$3")
      (value "HR911105A")
      (footprint "eagle-import:RJ45")
      (libsource (lib "eagle-import") (part "HR911105A"))
    )
    (comp (ref "U$5")
      (value "MICRO-USB-SHIELD-ZX62R-B-5P")
      (footprint "eagle-import:ZX62R-B-5P")
      (libsource (lib "eagle-import") (part "MICRO-USB-SHIELD-ZX62R-B-5P"))
    )
    (comp (ref "X1")
      (value "USB-B-S")
      (footprint "eagle-import:USB-B-SMT")
      (libsource (lib "eagle-import") (part "USB-B-S"))
    )
  )
  (nets
    (net (code "1") (name "+1V2") (class "Default")
      (node (ref "C41") (pin "1") (pinfunction "1_1") (pintype "passive"))
      (node (ref "C44") (pin "2") (pinfunction "2_2") (pintype "passive"))
      (node (ref "C52") (pin "1") (pinfunction "1_1") (pintype "passive"))
      (node (ref "C53") (pin "1") (pinfunction "1_1") (pintype "passive"))
      (node (ref "C54") (pin "1") (pinfunction "1_1") (pintype "passive"))
      (node (ref "C55") (pin "1") (pinfunction "1_1") (pintype "passive"))
      (node (ref "C56") (pin "1") (pinfunction "1_1") (pintype "passive"))
      (node (ref "C62") (pin "1") (pinfunction "1_1") (pintype "passive"))
      (node (ref "C63") (pin "1") (pinfunction "1_1") (pintype "passive"))
      (node (ref "C64") (pin "1") (pinfunction "1_1") (pintype "passive"))
      (node (ref "C65") (pin "1") (pinfunction "1_1") (pintype "passive"))
      (node (ref "C66") (pin "1") (pinfunction "1_1") (pintype "passive"))
      (node (ref "C67") (pin "1") (pinfunction "1_1") (pintype "passive"))
      (node (ref "JP12") (pin "4") (pinfunction "4_4") (pintype "passive"))
      (node (ref "L3") (pin "P$1") (pinfunction "1_P$1") (pintype "passive"))
      (node (ref "R7") (pin "1") (pinfunction "1_1") (pintype "passive"))
      (node (ref "U$1") (pin "108") (pinfunction "VDD-SYS1_108") (pintype "bidirectional"))
      (node (ref "U$1") (pin "126") (pinfunction "VDD-SYS2_126") (pintype "bidirectional"))
      (node (ref "U$1") (pin "19") (pinfunction "VDD-SYS3_19") (pintype "bidirectional"))
      (node (ref "U$1") (pin "20") (pinfunction "VDD-CPU3_20") (pintype "bidirectional"))
      (node (ref "U$1") (pin "21") (pinfunction "VDD-CPU2_21") (pintype "bidirectional"))
      (node (ref "U$1") (pin "25") (pinfunction "VDD-CPU1_25") (pintype "bidirectional"))
      (node (ref "U$1") (pin "26") (pinfunction "VDD-CPU0_26") (pintype "bidirectional"))
      (node (ref "U$1") (pin "38") (pinfunction "VDD-CPU4_38") (pintype "bidirectional"))
      (node (ref "U$1") (pin "47") (pinfunction "VDD-CPU5_47") (pintype "bidirectional"))
      (node (ref "U$1") (pin "51") (pinfunction "VDD-CPU6_51") (pintype "bidirectional"))
      (node (ref "U$1") (pin "56") (pinfunction "VDD-CPU7_56") (pintype "bidirectional"))
      (node (ref "U$1") (pin "58") (pinfunction "VDD-SYS4_58") (pintype "bidirectional"))
      (node (ref "U$1") (pin "64") (pinfunction "VDD-SYS5_64") (pintype "bidirectional"))
      (node (ref "U$1") (pin "80") (pinfunction "VDD-SYS0_80") (pintype "bidirectional"))
      (node (ref "U$1") (pin "88") (pinfunction "EPHY_VDD_88") (pintype "bidirectional"))
    )
    (net (code "2") (name "+1V8") (class "Default")
      (node (ref "C14") (pin "2") (pinfunction "2_2") (pintype "passive"))
      (node (ref "C38") (pin "2") (pinfunction "2_2") (pintype "passive"))
      (node (ref "C39") (pin "1") (pinfunction "1_1") (pintype "passive"))
      (node (ref "C42") (pin "1") (pinfunction "1_1") (pintype "passive"))
      (node (ref "C43") (pin "2") (pinfunction "2_2") (pintype "passive"))
      (node (ref "C47") (pin "1") (pinfunction "1_1") (pintype "passive"))
      (node (ref "C50") (pin "1") (pinfunction "1_1") (pintype "passive"))
      (node (ref "C51") (pin "1") (pinfunction "1_1") (pintype "passive"))
      (node (ref "JP12") (pin "6") (pinfunction "6_6") (pintype "passive"))
      (node (ref "L4") (pin "P$1") (pinfunction "1_P$1") (pintype "passive"))
      (node (ref "R13") (pin "2") (pinfunction "2_2") (pintype "passive"))
      (node (ref "R55") (pin "1") (pinfunction "1_1") (pintype "passive"))
      (node (ref "U$1") (pin "59") (pinfunction "VCC-DRAM8_59") (pintype "bidirectional"))
      (node (ref "U$1") (pin "60") (pinfunction "VCC-DRAM9_60") (pintype "bidirectional"))
      (node (ref "U$1") (pin "61") (pinfunction "VCC-DRAM10_61") (pintype "bidirectional"))
      (node (ref "U$1") (pin "62") (pinfunction "VCC-DRAM11_62") (pintype "bidirectional"))
      (node (ref "U$1") (pin "65") (pinfunction "VCC-DRAM0_65") (pintype "bidirectional"))
      (node (ref "U$1") (pin "66") (pinfunction "VCC-DRAM1_66") (pintype "bidirectional"))
      (node (ref "U$1") (pin "67") (pinfunction "VCC-DRAM2_67") (pintype "bidirectional"))
      (node (ref "U$1") (pin "68") (pinfunction "VCC-DRAM3_68") (pintype "bidirectional"))
      (node (ref "U$1") (pin "69") (pinfunction "VCC-DRAM4_69") (pintype "bidirectional"))
      (node (ref "U$1") (pin "70") (pinfunction "VCC-DRAM5_70") (pintype "bidirectional"))
      (node (ref "U$1") (pin "72") (pinfunction "VCC-DRAM6_72") (pintype "bidirectional"))
      (node (ref "U$1") (pin "79") (pinfunction "VCC-DRAM7_79") (pintype "bidirectional"))
    )
    (net (code "3") (name "+2V5") (class "Default")
      (node (ref "C76") (pin "1") (pinfunction "1_1") (pintype "passive"))
      (node (ref "JP3") (pin "1") (pinfunction "1_1") (pintype "passive"))
      (node (ref "U$6") (pin "5") (pinfunction "VOUT_5") (pintype "bidirectional"))
    )
    (net (code "4") (name "+3V3") (class "Default")
      (node (ref "C1") (pin "1") (pinfunction "1_1") (pintype "passive"))
      (node (ref "C2") (pin "1") (pinfunction "1_1") (pintype "passive"))
      (node (ref "C3") (pin "1") (pinfunction "1_1") (pintype "passive"))
      (node (ref "C30") (pin "1") (pinfunction "1_1") (pintype "passive"))
      (node (ref "C31") (pin "1") (pinfunction "1_1") (pintype "passive"))
      (node (ref "C45") (pin "1") (pinfunction "1_1") (pintype "passive"))
      (node (ref "C46") (pin "2") (pinfunction "2_2") (pintype "passive"))
      (node (ref "C57") (pin "1") (pinfunction "1_1") (pintype "passive"))
      (node (ref "C58") (pin "1") (pinfunction "1_1") (pintype "passive"))
      (node (ref "C59") (pin "1") (pinfunction "1_1") (pintype "passive"))
      (node (ref "C60") (pin "1") (pinfunction "1_1") (pintype "passive"))
      (node (ref "C61") (pin "1") (pinfunction "1_1") (pintype "passive"))
      (node (ref "C69") (pin "1") (pinfunction "1_1") (pintype "passive"))
      (node (ref "C70") (pin "1") (pinfunction "1_1") (pintype "passive"))
      (node (ref "C9") (pin "1") (pinfunction "1_1") (pintype "passive"))
      (node (ref "IC3") (pin "3") (pinfunction "RST_3") (pintype "bidirectional"))
      (node (ref "IC3") (pin "5") (pinfunction "WP_5") (pintype "bidirectional"))
      (node (ref "IC3") (pin "6") (pinfunction "VCC_6") (pintype "bidirectional"))
      (node (ref "J1") (pin "4") (pinfunction "VDD_4") (pintype "power_in"))
      (node (ref "J3") (pin "31") (pinfunction "MS_31") (pintype "passive"))
      (node (ref "J3") (pin "4") (pinfunction "MS_4") (pintype "passive"))
      (node (ref "J4") (pin "1") (pinfunction "15_1") (pintype "passive"))
      (node (ref "JP1") (pin "1") (pinfunction "1_1") (pintype "passive"))
      (node (ref "JP1") (pin "17") (pinfunction "17_17") (pintype "passive"))
      (node (ref "JP10") (pin "1") (pinfunction "1_1") (pintype "passive"))
      (node (ref "JP10") (pin "17") (pinfunction "17_17") (pintype "passive"))
      (node (ref "JP12") (pin "5") (pinfunction "5_5") (pintype "passive"))
      (node (ref "JP12") (pin "7") (pinfunction "7_7") (pintype "passive"))
      (node (ref "JP3") (pin "3") (pinfunction "3_3") (pintype "passive"))
      (node (ref "JP5") (pin "1") (pinfunction "1_1") (pintype "passive"))
      (node (ref "JP6") (pin "1") (pinfunction "1_1") (pintype "passive"))
      (node (ref "L2") (pin "1") (pinfunction "1_1") (pintype "passive"))
      (node (ref "L5") (pin "P$1") (pinfunction "1_P$1") (pintype "passive"))
      (node (ref "R1") (pin "2") (pinfunction "2_2") (pintype "passive"))
      (node (ref "R10") (pin "2") (pinfunction "2_2") (pintype "passive"))
      (node (ref "R11") (pin "2") (pinfunction "2_2") (pintype "passive"))
      (node (ref "R19") (pin "2") (pinfunction "2_2") (pintype "passive"))
      (node (ref "R2") (pin "2") (pinfunction "2_2") (pintype "passive"))
      (node (ref "R32") (pin "1") (pinfunction "1_1") (pintype "passive"))
      (node (ref "R36") (pin "1") (pinfunction "1_1") (pintype "passive"))
      (node (ref "R38") (pin "1") (pinfunction "1_1") (pintype "passive"))
      (node (ref "R39") (pin "1") (pinfunction "1_1") (pintype "passive"))
      (node (ref "R57") (pin "1") (pinfunction "1_1") (pintype "passive"))
      (node (ref "R8") (pin "1") (pinfunction "1_1") (pintype "passive"))
      (node (ref "R9") (pin "1") (pinfunction "1_1") (pintype "passive"))
      (node (ref "RN1") (pin "1") (pinfunction "1_1") (pintype "passive"))
      (node (ref "RN1") (pin "2") (pinfunction "1_2") (pintype "passive"))
      (node (ref "RN1") (pin "3") (pinfunction "1_3") (pintype "passive"))
      (node (ref "RN1") (pin "4") (pinfunction "1_4") (pintype "passive"))
      (node (ref "RN2") (pin "1") (pinfunction "1_1") (pintype "passive"))
      (node (ref "RN2") (pin "2") (pinfunction "1_2") (pintype "passive"))
      (node (ref "RN2") (pin "3") (pinfunction "1_3") (pintype "passive"))
      (node (ref "RN2") (pin "4") (pinfunction "1_4") (pintype "passive"))
      (node (ref "U$1") (pin "104") (pinfunction "VCC-0_104") (pintype "bidirectional"))
      (node (ref "U$1") (pin "109") (pinfunction "VCC-USB_109") (pintype "bidirectional"))
      (node (ref "U$1") (pin "122") (pinfunction "HPVCCIN_122") (pintype "bidirectional"))
      (node (ref "U$1") (pin "127") (pinfunction "VCC-1_127") (pintype "bidirectional"))
      (node (ref "U$1") (pin "50") (pinfunction "VCC-3_50") (pintype "bidirectional"))
      (node (ref "U$1") (pin "57") (pinfunction "VCC-2_57") (pintype "bidirectional"))
      (node (ref "U$1") (pin "85") (pinfunction "VCC-MCSI_85") (pintype "bidirectional"))
      (node (ref "U$1") (pin "93") (pinfunction "EPHY_VCC_93") (pintype "bidirectional"))
      (node (ref "U$2") (pin "P$22") (pinfunction "VDD_IO_P$22") (pintype "bidirectional"))
      (node (ref "U$2") (pin "P$9") (pinfunction "VCC_P$9") (pintype "bidirectional"))
      (node (ref "U$6") (pin "1") (pinfunction "VIN_1") (pintype "bidirectional"))
      (node (ref "U$6") (pin "3") (pinfunction "CE_3") (pintype "bidirectional"))
      (node (ref "U$8") (pin "1") (pinfunction "VDD_1") (pintype "bidirectional"))
      (node (ref "X3") (pin "2") (pinfunction "S_2") (pintype "passive"))
    )
    (net (code "5") (name "+3V3A") (class "Default")
      (node (ref "C16") (pin "2") (pinfunction "2_2") (pintype "passive"))
      (node (ref "C19") (pin "2") (pinfunction "2_2") (pintype "passive"))
      (node (ref "C26") (pin "2") (pinfunction "2_2") (pintype "passive"))
      (node (ref "C37") (pin "1") (pinfunction "1_1") (pintype "passive"))
      (node (ref "C68") (pin "1") (pinfunction "1_1") (pintype "passive"))
      (node (ref "C71") (pin "1") (pinfunction "1_1") (pintype "passive"))
      (node (ref "C72") (pin "1") (pinfunction "1_1") (pintype "passive"))
      (node (ref "IC1") (pin "2") (pinfunction "OUT_2") (pintype "passive"))
      (node (ref "R29") (pin "2") (pinfunction "2_2") (pintype "passive"))
      (node (ref "R30") (pin "2") (pinfunction "2_2") (pintype "passive"))
      (node (ref "U$1") (pin "115") (pinfunction "AVCC_115") (pintype "bidirectional"))
      (node (ref "U$1") (pin "76") (pinfunction "VCC-PLL_76") (pintype "bidirectional"))
    )
    (net (code "6") (name "+3V3ANC") (class "Default")
      (node (ref "IC1") (pin "4") (pinfunction "IN1_4") (pintype "input"))
    )
    (net (code "7") (name "+5V") (class "Default")
      (node (ref "C32") (pin "1") (pinfunction "1_1") (pintype "passive"))
      (node (ref "C33") (pin "1") (pinfunction "1_1") (pintype "passive"))
      (node (ref "C35") (pin "1") (pinfunction "1_1") (pintype "passive"))
      (node (ref "C36") (pin "1") (pinfunction "1_1") (pintype "passive"))
      (node (ref "C40") (pin "1") (pinfunction "1_1") (pintype "passive"))
      (node (ref "C73") (pin "1") (pinfunction "1_1") (pintype "passive"))
      (node (ref "IC1") (pin "3") (pinfunction "IN_3") (pintype "input"))
      (node (ref "JP1") (pin "2") (pinfunction "2_2") (pintype "passive"))
      (node (ref "JP1") (pin "4") (pinfunction "4_4") (pintype "passive"))
      (node (ref "L1") (pin "P$1") (pinfunction "1_P$1") (pintype "passive"))
      (node (ref "R16") (pin "2") (pinfunction "2_2") (pintype "passive"))
      (node (ref "U$4") (pin "10") (pinfunction "VIN1_10") (pintype "bidirectional"))
      (node (ref "U$4") (pin "16") (pinfunction "VCC_16") (pintype "bidirectional"))
      (node (ref "U$4") (pin "18") (pinfunction "EN3_18") (pintype "bidirectional"))
      (node (ref "U$4") (pin "19") (pinfunction "VIN3_19") (pintype "bidirectional"))
      (node (ref "U$4") (pin "7") (pinfunction "VIN2_7") (pintype "bidirectional"))
      (node (ref "U$4") (pin "8") (pinfunction "EN2_8") (pintype "bidirectional"))
      (node (ref "U$4") (pin "9") (pinfunction "EN1_9") (pintype "bidirectional"))
      (node (ref "U$5") (pin "1") (pinfunction "1_1") (pintype "input"))
      (node (ref "U$7") (pin "2") (pinfunction "S_2") (pintype "passive"))
      (node (ref "U$9") (pin "6") (pinfunction "IN_6") (pintype "bidirectional"))
      (node (ref "X1") (pin "VUSB") (pinfunction "VBUS_VUSB") (pintype "bidirectional"))
      (node (ref "X3") (pin "1") (pinfunction "S_1") (pintype "passive"))
    )
    (net (code "8") (name "BT_H_WK") (class "Default")
      (node (ref "U$2") (pin "P$7") (pinfunction "BT_H_WK_P$7") (pintype "bidirectional"))
    )
    (net (code "9") (name "BT_WK") (class "Default")
      (node (ref "U$2") (pin "P$6") (pinfunction "BT_WK_P$6") (pintype "bidirectional"))
    )
    (net (code "10") (name "CSI_D0{slash}LCD_D2") (class "Default")
      (node (ref "J3") (pin "23") (pinfunction "MS_23") (pintype "passive"))
      (node (ref "JP10") (pin "20") (pinfunction "20_20") (pintype "passive"))
      (node (ref "JP11") (pin "12") (pinfunction "12_12") (pintype "passive"))
      (node (ref "JP6") (pin "16") (pinfunction "16_16") (pintype "passive"))
      (node (ref "U$1") (pin "33") (pinfunction "PE4/CSI-D0/LCD-D2_33") (pintype "bidirectional"))
      (node (ref "X3") (pin "14") (pinfunction "S_14") (pintype "passive"))
    )
    (net (code "11") (name "CSI_D1{slash}LCD_D3") (class "Default")
      (node (ref "J3") (pin "24") (pinfunction "MS_24") (pintype "passive"))
      (node (ref "JP10") (pin "19") (pinfunction "19_19") (pintype "passive"))
      (node (ref "JP11") (pin "11") (pinfunction "11_11") (pintype "passive"))
      (node (ref "JP6") (pin "15") (pinfunction "15_15") (pintype "passive"))
      (node (ref "U$1") (pin "32") (pinfunction "PE5/CSI-D1/-LCD-D3_32") (pintype "bidirectional"))
      (node (ref "X3") (pin "15") (pinfunction "S_15") (pintype "passive"))
    )
    (net (code "12") (name "CSI_D2{slash}LCD_D4") (class "Default")
      (node (ref "J3") (pin "25") (pinfunction "MS_25") (pintype "passive"))
      (node (ref "JP10") (pin "16") (pinfunction "16_16") (pintype "passive"))
      (node (ref "JP11") (pin "10") (pinfunction "10_10") (pintype "passive"))
      (node (ref "JP6") (pin "14") (pinfunction "14_14") (pintype "passive"))
      (node (ref "U$1") (pin "31") (pinfunction "PE6/CSI-D2/LCD-D4_31") (pintype "bidirectional"))
      (node (ref "X3") (pin "12") (pinfunction "S_12") (pintype "passive"))
    )
    (net (code "13") (name "CSI_D3{slash}LCD_D5") (class "Default")
      (node (ref "J3") (pin "26") (pinfunction "MS_26") (pintype "passive"))
      (node (ref "JP10") (pin "15") (pinfunction "15_15") (pintype "passive"))
      (node (ref "JP11") (pin "9") (pinfunction "9_9") (pintype "passive"))
      (node (ref "JP6") (pin "13") (pinfunction "13_13") (pintype "passive"))
      (node (ref "U$1") (pin "30") (pinfunction "PE7/CSI-D3/LCD-D5_30") (pintype "bidirectional"))
      (node (ref "X3") (pin "13") (pinfunction "S_13") (pintype "passive"))
    )
    (net (code "14") (name "CSI_D4{slash}LCD_D6") (class "Default")
      (node (ref "J3") (pin "27") (pinfunction "MS_27") (pintype "passive"))
      (node (ref "JP10") (pin "14") (pinfunction "14_14") (pintype "passive"))
      (node (ref "JP11") (pin "8") (pinfunction "8_8") (pintype "passive"))
      (node (ref "JP6") (pin "12") (pinfunction "12_12") (pintype "passive"))
      (node (ref "U$1") (pin "28") (pinfunction "PE8/CSI-D4/LCD-D6_28") (pintype "bidirectional"))
      (node (ref "X3") (pin "10") (pinfunction "S_10") (pintype "passive"))
    )
    (net (code "15") (name "CSI_D5{slash}LCD_D7") (class "Default")
      (node (ref "J3") (pin "28") (pinfunction "MS_28") (pintype "passive"))
      (node (ref "JP10") (pin "13") (pinfunction "13_13") (pintype "passive"))
      (node (ref "JP11") (pin "7") (pinfunction "7_7") (pintype "passive"))
      (node (ref "JP6") (pin "11") (pinfunction "11_11") (pintype "passive"))
      (node (ref "U$1") (pin "27") (pinfunction "PE9/CSI-D5/LCD-D7_27") (pintype "bidirectional"))
      (node (ref "X3") (pin "11") (pinfunction "S_11") (pintype "passive"))
    )
    (net (code "16") (name "CSI_D6{slash}LCD_D10") (class "Default")
      (node (ref "J3") (pin "15") (pinfunction "MS_15") (pintype "passive"))
      (node (ref "JP10") (pin "12") (pinfunction "12_12") (pintype "passive"))
      (node (ref "JP11") (pin "6") (pinfunction "6_6") (pintype "passive"))
      (node (ref "JP6") (pin "10") (pinfunction "10_10") (pintype "passive"))
      (node (ref "U$1") (pin "24") (pinfunction "PE10/CSI-D6/LCD-D10_24") (pintype "bidirectional"))
      (node (ref "X3") (pin "8") (pinfunction "S_8") (pintype "passive"))
    )
    (net (code "17") (name "CSI_D7{slash}LCD_D11") (class "Default")
      (node (ref "J3") (pin "16") (pinfunction "MS_16") (pintype "passive"))
      (node (ref "JP10") (pin "11") (pinfunction "11_11") (pintype "passive"))
      (node (ref "JP11") (pin "5") (pinfunction "5_5") (pintype "passive"))
      (node (ref "JP6") (pin "9") (pinfunction "9_9") (pintype "passive"))
      (node (ref "U$1") (pin "23") (pinfunction "PE11/CSI-D7/LCD-D11_23") (pintype "bidirectional"))
      (node (ref "X3") (pin "9") (pinfunction "S_9") (pintype "passive"))
    )
    (net (code "18") (name "CSI_D8{slash}LCD_D12") (class "Default")
      (node (ref "J3") (pin "17") (pinfunction "MS_17") (pintype "passive"))
      (node (ref "JP10") (pin "10") (pinfunction "10_10") (pintype "passive"))
      (node (ref "JP11") (pin "4") (pinfunction "4_4") (pintype "passive"))
      (node (ref "U$1") (pin "22") (pinfunction "PE12/CSI-D8/LCD-D12_22") (pintype "bidirectional"))
      (node (ref "X3") (pin "6") (pinfunction "S_6") (pintype "passive"))
    )
    (net (code "19") (name "CSI_D9{slash}LCD_D13") (class "Default")
      (node (ref "J3") (pin "18") (pinfunction "MS_18") (pintype "passive"))
      (node (ref "JP10") (pin "9") (pinfunction "9_9") (pintype "passive"))
      (node (ref "JP11") (pin "3") (pinfunction "3_3") (pintype "passive"))
      (node (ref "U$1") (pin "18") (pinfunction "PE13/CSI-D9/LCD-D13_18") (pintype "bidirectional"))
      (node (ref "X3") (pin "7") (pinfunction "S_7") (pintype "passive"))
    )
    (net (code "20") (name "CSI_D10{slash}LCD_D14") (class "Default")
      (node (ref "J3") (pin "19") (pinfunction "MS_19") (pintype "passive"))
      (node (ref "JP11") (pin "2") (pinfunction "2_2") (pintype "passive"))
      (node (ref "U$1") (pin "17") (pinfunction "PE14/CSI-D10/LCD-D14_17") (pintype "bidirectional"))
      (node (ref "X3") (pin "4") (pinfunction "S_4") (pintype "passive"))
    )
    (net (code "21") (name "CSI_D11{slash}LCD_D15") (class "Default")
      (node (ref "J3") (pin "20") (pinfunction "MS_20") (pintype "passive"))
      (node (ref "JP11") (pin "1") (pinfunction "1_1") (pintype "passive"))
      (node (ref "U$1") (pin "16") (pinfunction "PE15/CSI-D11/LCD-D15_16") (pintype "bidirectional"))
      (node (ref "X3") (pin "5") (pinfunction "S_5") (pintype "passive"))
    )
    (net (code "22") (name "CSI_D12{slash}LCD_D18") (class "Default")
      (node (ref "J3") (pin "7") (pinfunction "MS_7") (pintype "passive"))
      (node (ref "JP12") (pin "15") (pinfunction "15_15") (pintype "passive"))
      (node (ref "U$1") (pin "15") (pinfunction "PE16/CSI-D12/LCD-D18_15") (pintype "bidirectional"))
      (node (ref "X3") (pin "22") (pinfunction "S_22") (pintype "passive"))
    )
    (net (code "23") (name "CSI_HSYNC{slash}LCD_HSYNC") (class "Default")
      (node (ref "J3") (pin "32") (pinfunction "MS_32") (pintype "passive"))
      (node (ref "JP10") (pin "6") (pinfunction "6_6") (pintype "passive"))
      (node (ref "JP11") (pin "14") (pinfunction "14_14") (pintype "passive"))
      (node (ref "JP6") (pin "6") (pinfunction "6_6") (pintype "passive"))
      (node (ref "U$1") (pin "35") (pinfunction "PE2/CSI-HSYNC/LCD-HSYNC_35") (pintype "bidirectional"))
      (node (ref "X3") (pin "17") (pinfunction "S_17") (pintype "passive"))
    )
    (net (code "24") (name "CSI_MCLK{slash}LCD_DE") (class "Default")
      (node (ref "J3") (pin "34") (pinfunction "MS_34") (pintype "passive"))
      (node (ref "JP10") (pin "8") (pinfunction "8_8") (pintype "passive"))
      (node (ref "JP11") (pin "15") (pinfunction "15_15") (pintype "passive"))
      (node (ref "JP6") (pin "8") (pinfunction "8_8") (pintype "passive"))
      (node (ref "U$1") (pin "36") (pinfunction "PE1/CSI-MCLK/LCD-DE_36") (pintype "bidirectional"))
      (node (ref "X3") (pin "20") (pinfunction "S_20") (pintype "passive"))
    )
    (net (code "25") (name "CSI_PCLK{slash}LCD_CLK") (class "Default")
      (node (ref "J3") (pin "30") (pinfunction "MS_30") (pintype "passive"))
      (node (ref "JP10") (pin "7") (pinfunction "7_7") (pintype "passive"))
      (node (ref "JP11") (pin "16") (pinfunction "16_16") (pintype "passive"))
      (node (ref "JP6") (pin "7") (pinfunction "7_7") (pintype "passive"))
      (node (ref "U$1") (pin "37") (pinfunction "PE0/CSI-CLK-/LCD-CLK_37") (pintype "bidirectional"))
      (node (ref "X3") (pin "21") (pinfunction "S_21") (pintype "passive"))
    )
    (net (code "26") (name "CSI_VSYNC{slash}LCD_VSYNC") (class "Default")
      (node (ref "J3") (pin "33") (pinfunction "MS_33") (pintype "passive"))
      (node (ref "JP10") (pin "5") (pinfunction "5_5") (pintype "passive"))
      (node (ref "JP11") (pin "13") (pinfunction "13_13") (pintype "passive"))
      (node (ref "JP6") (pin "5") (pinfunction "5_5") (pintype "passive"))
      (node (ref "U$1") (pin "34") (pinfunction "PE3/CSI-VSYNC/LCD-VSYNC_34") (pintype "bidirectional"))
      (node (ref "X3") (pin "16") (pinfunction "S_16") (pintype "passive"))
    )
    (net (code "27") (name "EPHY_RXN") (class "Default")
      (node (ref "R41") (pin "1") (pinfunction "1_1") (pintype "passive"))
      (node (ref "U$1") (pin "89") (pinfunction "EPHY_RXN_89") (pintype "bidirectional"))
      (node (ref "U$3") (pin "6") (pinfunction "RD-_6") (pintype "bidirectional"))
    )
    (net (code "28") (name "EPHY_RXP") (class "Default")
      (node (ref "R40") (pin "1") (pinfunction "1_1") (pintype "passive"))
      (node (ref "U$1") (pin "90") (pinfunction "EPHY_RXP_90") (pintype "bidirectional"))
      (node (ref "U$3") (pin "3") (pinfunction "RD+_3") (pintype "bidirectional"))
    )
    (net (code "29") (name "EPHY_TXN") (class "Default")
      (node (ref "R43") (pin "1") (pinfunction "1_1") (pintype "passive"))
      (node (ref "U$1") (pin "91") (pinfunction "EPHY_TXN_91") (pintype "bidirectional"))
      (node (ref "U$3") (pin "2") (pinfunction "TD-_2") (pintype "bidirectional"))
    )
    (net (code "30") (name "EPHY_TXP") (class "Default")
      (node (ref "R42") (pin "1") (pinfunction "1_1") (pintype "passive"))
      (node (ref "U$1") (pin "92") (pinfunction "EPHY_TXP_92") (pintype "bidirectional"))
      (node (ref "U$3") (pin "1") (pinfunction "TD+_1") (pintype "bidirectional"))
    )
    (net (code "31") (name "GND") (class "Default")
      (node (ref "ANT1") (pin "1") (pinfunction "1_1") (pintype "passive"))
      (node (ref "C1") (pin "2") (pinfunction "2_2") (pintype "passive"))
      (node (ref "C10") (pin "2") (pinfunction "2_2") (pintype "passive"))
      (node (ref "C11") (pin "1") (pinfunction "1_1") (pintype "passive"))
      (node (ref "C12") (pin "1") (pinfunction "1_1") (pintype "passive"))
      (node (ref "C13") (pin "2") (pinfunction "2_2") (pintype "passive"))
      (node (ref "C15") (pin "1") (pinfunction "1_1") (pintype "passive"))
      (node (ref "C16") (pin "1") (pinfunction "1_1") (pintype "passive"))
      (node (ref "C17") (pin "2") (pinfunction "2_2") (pintype "passive"))
      (node (ref "C19") (pin "1") (pinfunction "1_1") (pintype "passive"))
      (node (ref "C2") (pin "2") (pinfunction "2_2") (pintype "passive"))
      (node (ref "C20") (pin "1") (pinfunction "1_1") (pintype "passive"))
      (node (ref "C21") (pin "1") (pinfunction "1_1") (pintype "passive"))
      (node (ref "C22") (pin "2") (pinfunction "2_2") (pintype "passive"))
      (node (ref "C23") (pin "1") (pinfunction "1_1") (pintype "passive"))
      (node (ref "C24") (pin "1") (pinfunction "1_1") (pintype "passive"))
      (node (ref "C26") (pin "1") (pinfunction "1_1") (pintype "passive"))
      (node (ref "C29") (pin "1") (pinfunction "1_1") (pintype "passive"))
      (node (ref "C3") (pin "2") (pinfunction "2_2") (pintype "passive"))
      (node (ref "C30") (pin "2") (pinfunction "2_2") (pintype "passive"))
      (node (ref "C31") (pin "2") (pinfunction "2_2") (pintype "passive"))
      (node (ref "C32") (pin "2") (pinfunction "2_2") (pintype "passive"))
      (node (ref "C33") (pin "2") (pinfunction "2_2") (pintype "passive"))
      (node (ref "C34") (pin "1") (pinfunction "1_1") (pintype "passive"))
      (node (ref "C35") (pin "2") (pinfunction "2_2") (pintype "passive"))
      (node (ref "C36") (pin "2") (pinfunction "2_2") (pintype "passive"))
      (node (ref "C37") (pin "2") (pinfunction "2_2") (pintype "passive"))
      (node (ref "C38") (pin "1") (pinfunction "1_1") (pintype "passive"))
      (node (ref "C39") (pin "2") (pinfunction "2_2") (pintype "passive"))
      (node (ref "C40") (pin "2") (pinfunction "2_2") (pintype "passive"))
      (node (ref "C43") (pin "1") (pinfunction "1_1") (pintype "passive"))
      (node (ref "C44") (pin "1") (pinfunction "1_1") (pintype "passive"))
      (node (ref "C46") (pin "1") (pinfunction "1_1") (pintype "passive"))
      (node (ref "C47") (pin "2") (pinfunction "2_2") (pintype "passive"))
      (node (ref "C48") (pin "2") (pinfunction "2_2") (pintype "passive"))
      (node (ref "C49") (pin "2") (pinfunction "2_2") (pintype "passive"))
      (node (ref "C5") (pin "2") (pinfunction "2_2") (pintype "passive"))
      (node (ref "C50") (pin "2") (pinfunction "2_2") (pintype "passive"))
      (node (ref "C51") (pin "2") (pinfunction "2_2") (pintype "passive"))
      (node (ref "C52") (pin "2") (pinfunction "2_2") (pintype "passive"))
      (node (ref "C53") (pin "2") (pinfunction "2_2") (pintype "passive"))
      (node (ref "C54") (pin "2") (pinfunction "2_2") (pintype "passive"))
      (node (ref "C55") (pin "2") (pinfunction "2_2") (pintype "passive"))
      (node (ref "C56") (pin "2") (pinfunction "2_2") (pintype "passive"))
      (node (ref "C57") (pin "2") (pinfunction "2_2") (pintype "passive"))
      (node (ref "C58") (pin "2") (pinfunction "2_2") (pintype "passive"))
      (node (ref "C59") (pin "2") (pinfunction "2_2") (pintype "passive"))
      (node (ref "C6") (pin "2") (pinfunction "2_2") (pintype "passive"))
      (node (ref "C60") (pin "2") (pinfunction "2_2") (pintype "passive"))
      (node (ref "C61") (pin "2") (pinfunction "2_2") (pintype "passive"))
      (node (ref "C62") (pin "2") (pinfunction "2_2") (pintype "passive"))
      (node (ref "C63") (pin "2") (pinfunction "2_2") (pintype "passive"))
      (node (ref "C64") (pin "2") (pinfunction "2_2") (pintype "passive"))
      (node (ref "C65") (pin "2") (pinfunction "2_2") (pintype "passive"))
      (node (ref "C66") (pin "2") (pinfunction "2_2") (pintype "passive"))
      (node (ref "C67") (pin "2") (pinfunction "2_2") (pintype "passive"))
      (node (ref "C68") (pin "2") (pinfunction "2_2") (pintype "passive"))
      (node (ref "C69") (pin "2") (pinfunction "2_2") (pintype "passive"))
      (node (ref "C7") (pin "2") (pinfunction "2_2") (pintype "passive"))
      (node (ref "C70") (pin "2") (pinfunction "2_2") (pintype "passive"))
      (node (ref "C71") (pin "2") (pinfunction "2_2") (pintype "passive"))
      (node (ref "C72") (pin "2") (pinfunction "2_2") (pintype "passive"))
      (node (ref "C73") (pin "2") (pinfunction "2_2") (pintype "passive"))
      (node (ref "C74") (pin "2") (pinfunction "2_2") (pintype "passive"))
      (node (ref "C75") (pin "2") (pinfunction "2_2") (pintype "passive"))
      (node (ref "C76") (pin "2") (pinfunction "2_2") (pintype "passive"))
      (node (ref "C8") (pin "2") (pinfunction "2_2") (pintype "passive"))
      (node (ref "C9") (pin "2") (pinfunction "2_2") (pintype "passive"))
      (node (ref "CN2") (pin "GND") (pinfunction "GND_GND") (pintype "power_in"))
      (node (ref "CN2") (pin "GNDBREAK") (pinfunction "GNDBREAK_GNDBREAK") (pintype "power_in"))
      (node (ref "IC1") (pin "1") (pinfunction "GND_1") (pintype "input"))
      (node (ref "IC3") (pin "7") (pinfunction "GND_7") (pintype "bidirectional"))
      (node (ref "J1") (pin "6") (pinfunction "GND_6") (pintype "power_in"))
      (node (ref "J1") (pin "S1") (pinfunction "S_S1") (pintype "passive"))
      (node (ref "J1") (pin "S2") (pinfunction "S_S2") (pintype "passive"))
      (node (ref "J1") (pin "S3") (pinfunction "S_S3") (pintype "passive"))
      (node (ref "J1") (pin "S4") (pinfunction "S_S4") (pintype "passive"))
      (node (ref "J3") (pin "13") (pinfunction "MS_13") (pintype "passive"))
      (node (ref "J3") (pin "14") (pinfunction "MS_14") (pintype "passive"))
      (node (ref "J3") (pin "21") (pinfunction "MS_21") (pintype "passive"))
      (node (ref "J3") (pin "22") (pinfunction "MS_22") (pintype "passive"))
      (node (ref "J3") (pin "29") (pinfunction "MS_29") (pintype "passive"))
      (node (ref "J3") (pin "3") (pinfunction "MS_3") (pintype "passive"))
      (node (ref "J3") (pin "36") (pinfunction "MS_36") (pintype "passive"))
      (node (ref "J3") (pin "5") (pinfunction "MS_5") (pintype "passive"))
      (node (ref "J3") (pin "6") (pinfunction "MS_6") (pintype "passive"))
      (node (ref "J4") (pin "12") (pinfunction "4_12") (pintype "passive"))
      (node (ref "J4") (pin "15") (pinfunction "1_15") (pintype "passive"))
      (node (ref "J4") (pin "6") (pinfunction "10_6") (pintype "passive"))
      (node (ref "J4") (pin "9") (pinfunction "7_9") (pintype "passive"))
      (node (ref "JP1") (pin "14") (pinfunction "14_14") (pintype "passive"))
      (node (ref "JP1") (pin "20") (pinfunction "20_20") (pintype "passive"))
      (node (ref "JP1") (pin "25") (pinfunction "25_25") (pintype "passive"))
      (node (ref "JP1") (pin "6") (pinfunction "6_6") (pintype "passive"))
      (node (ref "JP1") (pin "9") (pinfunction "9_9") (pintype "passive"))
      (node (ref "JP10") (pin "18") (pinfunction "18_18") (pintype "passive"))
      (node (ref "JP10") (pin "2") (pinfunction "2_2") (pintype "passive"))
      (node (ref "JP12") (pin "1") (pinfunction "1_1") (pintype "passive"))
      (node (ref "JP12") (pin "16") (pinfunction "16_16") (pintype "passive"))
      (node (ref "JP12") (pin "2") (pinfunction "2_2") (pintype "passive"))
      (node (ref "JP12") (pin "3") (pinfunction "3_3") (pintype "passive"))
      (node (ref "JP5") (pin "3") (pinfunction "3_3") (pintype "passive"))
      (node (ref "JP6") (pin "17") (pinfunction "17_17") (pintype "passive"))
      (node (ref "JP6") (pin "18") (pinfunction "18_18") (pintype "passive"))
      (node (ref "JP6") (pin "2") (pinfunction "2_2") (pintype "passive"))
      (node (ref "LED1") (pin "C") (pinfunction "C_C") (pintype "passive"))
      (node (ref "LED2") (pin "C") (pinfunction "C_C") (pintype "passive"))
      (node (ref "R12") (pin "2") (pinfunction "2_2") (pintype "passive"))
      (node (ref "R14") (pin "1") (pinfunction "1_1") (pintype "passive"))
      (node (ref "R15") (pin "1") (pinfunction "1_1") (pintype "passive"))
      (node (ref "R24") (pin "2") (pinfunction "2_2") (pintype "passive"))
      (node (ref "R27") (pin "1") (pinfunction "1_1") (pintype "passive"))
      (node (ref "R28") (pin "2") (pinfunction "2_2") (pintype "passive"))
      (node (ref "R46") (pin "2") (pinfunction "2_2") (pintype "passive"))
      (node (ref "R47") (pin "2") (pinfunction "2_2") (pintype "passive"))
      (node (ref "R54") (pin "1") (pinfunction "1_1") (pintype "passive"))
      (node (ref "R56") (pin "1") (pinfunction "1_1") (pintype "passive"))
      (node (ref "R58") (pin "1") (pinfunction "1_1") (pintype "passive"))
      (node (ref "S1") (pin "1") (pinfunction "1_1") (pintype "passive"))
      (node (ref "S2") (pin "1") (pinfunction "1_1") (pintype "passive"))
      (node (ref "S3") (pin "1") (pinfunction "1_1") (pintype "passive"))
      (node (ref "S4") (pin "1") (pinfunction "1_1") (pintype "passive"))
      (node (ref "S5") (pin "1") (pinfunction "1_1") (pintype "passive"))
      (node (ref "U$1") (pin "116") (pinfunction "AGND_116") (pintype "bidirectional"))
      (node (ref "U$1") (pin "P$1") (pinfunction "PAD_P$1") (pintype "bidirectional"))
      (node (ref "U$2") (pin "P$1") (pinfunction "GND1_P$1") (pintype "bidirectional"))
      (node (ref "U$2") (pin "P$20") (pinfunction "GND20_P$20") (pintype "bidirectional"))
      (node (ref "U$2") (pin "P$3") (pinfunction "GND3_P$3") (pintype "bidirectional"))
      (node (ref "U$2") (pin "P$31") (pinfunction "GND31_P$31") (pintype "bidirectional"))
      (node (ref "U$2") (pin "P$33") (pinfunction "GND33_P$33") (pintype "bidirectional"))
      (node (ref "U$2") (pin "P$36") (pinfunction "GND36_P$36") (pintype "bidirectional"))
      (node (ref "U$2") (pin "P$41") (pinfunction "UART_RTS_P$41") (pintype "bidirectional"))
      (node (ref "U$3") (pin "10") (pinfunction "G-_10") (pintype "bidirectional"))
      (node (ref "U$3") (pin "11") (pinfunction "Y-_11") (pintype "bidirectional"))
      (node (ref "U$3") (pin "8") (pinfunction "GND_8") (pintype "bidirectional"))
      (node (ref "U$3") (pin "SHIELD1") (pinfunction "SHIELD0_SHIELD1") (pintype "bidirectional"))
      (node (ref "U$3") (pin "SHIELD2") (pinfunction "SHIELD1_SHIELD2") (pintype "bidirectional"))
      (node (ref "U$4") (pin "1") (pinfunction "GND3_1") (pintype "bidirectional"))
      (node (ref "U$4") (pin "12") (pinfunction "GND1_12") (pintype "bidirectional"))
      (node (ref "U$4") (pin "13") (pinfunction "GND1_13") (pintype "bidirectional"))
      (node (ref "U$4") (pin "15") (pinfunction "AGND_15") (pintype "bidirectional"))
      (node (ref "U$4") (pin "17") (pinfunction "AGND_17") (pintype "bidirectional"))
      (node (ref "U$4") (pin "21") (pinfunction "PAD_21") (pintype "bidirectional"))
      (node (ref "U$4") (pin "4") (pinfunction "GND2_4") (pintype "bidirectional"))
      (node (ref "U$4") (pin "5") (pinfunction "GND2_5") (pintype "bidirectional"))
      (node (ref "U$5") (pin "5") (pinfunction "5_5") (pintype "input"))
      (node (ref "U$5") (pin "M1") (pinfunction "S1_M1") (pintype "passive"))
      (node (ref "U$5") (pin "M2") (pinfunction "S2_M2") (pintype "passive"))
      (node (ref "U$5") (pin "M3") (pinfunction "S3_M3") (pintype "passive"))
      (node (ref "U$5") (pin "M4") (pinfunction "S4_M4") (pintype "passive"))
      (node (ref "U$6") (pin "2") (pinfunction "VSS_2") (pintype "bidirectional"))
      (node (ref "U$7") (pin "1") (pinfunction "G_1") (pintype "passive"))
      (node (ref "U$8") (pin "6") (pinfunction "GND_6") (pintype "bidirectional"))
      (node (ref "U$8") (pin "8") (pinfunction "A0_8") (pintype "bidirectional"))
      (node (ref "U$9") (pin "2") (pinfunction "GND_2") (pintype "bidirectional"))
      (node (ref "X1") (pin "GND") (pinfunction "GND_GND") (pintype "bidirectional"))
      (node (ref "X3") (pin "3") (pinfunction "S_3") (pintype "passive"))
    )
    (net (code "32") (name "HP_COM") (class "Default")
      (node (ref "C18") (pin "2") (pinfunction "2_2") (pintype "passive"))
      (node (ref "J2") (pin "RING2") (pinfunction "RING2_RING2") (pintype "bidirectional"))
      (node (ref "R26") (pin "2") (pinfunction "2_2") (pintype "passive"))
      (node (ref "U$1") (pin "125") (pinfunction "HPCOM_125") (pintype "bidirectional"))
    )
    (net (code "33") (name "HP_COMFB") (class "Default")
      (node (ref "R26") (pin "1") (pinfunction "1_1") (pintype "passive"))
      (node (ref "U$1") (pin "124") (pinfunction "HPCOMFB_124") (pintype "bidirectional"))
    )
    (net (code "34") (name "HP_L") (class "Default")
      (node (ref "J2") (pin "TIP") (pinfunction "TIP_TIP") (pintype "bidirectional"))
      (node (ref "U$1") (pin "121") (pinfunction "HPOUTL_121") (pintype "bidirectional"))
    )
    (net (code "35") (name "HP_R") (class "Default")
      (node (ref "J2") (pin "RING1") (pinfunction "RING1_RING1") (pintype "bidirectional"))
      (node (ref "U$1") (pin "120") (pinfunction "HPOUTR_120") (pintype "bidirectional"))
    )
    (net (code "36") (name "I2C0{slash}SCL") (class "Default")
      (node (ref "JP1") (pin "5") (pinfunction "5_5") (pintype "passive"))
      (node (ref "U$1") (pin "45") (pinfunction "PB6/I2C0/SCL_45") (pintype "bidirectional"))
    )
    (net (code "37") (name "I2C0{slash}SDA") (class "Default")
      (node (ref "JP1") (pin "3") (pinfunction "3_3") (pintype "passive"))
      (node (ref "U$1") (pin "46") (pinfunction "PB7/I2C0/SDA_46") (pintype "bidirectional"))
    )
    (net (code "38") (name "I2C1{slash}SCL") (class "Default")
      (node (ref "J4") (pin "3") (pinfunction "13_3") (pintype "passive"))
      (node (ref "JP1") (pin "26") (pinfunction "26_26") (pintype "passive"))
      (node (ref "JP10") (pin "3") (pinfunction "3_3") (pintype "passive"))
      (node (ref "JP12") (pin "11") (pinfunction "11_11") (pintype "passive"))
      (node (ref "JP6") (pin "3") (pinfunction "3_3") (pintype "passive"))
      (node (ref "R38") (pin "2") (pinfunction "2_2") (pintype "passive"))
      (node (ref "R44") (pin "2") (pinfunction "2_2") (pintype "passive"))
      (node (ref "U$1") (pin "9") (pinfunction "PE21/UART1/TX_9") (pintype "bidirectional"))
      (node (ref "U$8") (pin "10") (pinfunction "SCL_10") (pintype "bidirectional"))
      (node (ref "X3") (pin "19") (pinfunction "S_19") (pintype "passive"))
    )
    (net (code "39") (name "I2C1{slash}SDA") (class "Default")
      (node (ref "J4") (pin "2") (pinfunction "14_2") (pintype "passive"))
      (node (ref "JP1") (pin "22") (pinfunction "22_22") (pintype "passive"))
      (node (ref "JP10") (pin "4") (pinfunction "4_4") (pintype "passive"))
      (node (ref "JP12") (pin "10") (pinfunction "10_10") (pintype "passive"))
      (node (ref "JP6") (pin "4") (pinfunction "4_4") (pintype "passive"))
      (node (ref "R39") (pin "2") (pinfunction "2_2") (pintype "passive"))
      (node (ref "R45") (pin "2") (pinfunction "2_2") (pintype "passive"))
      (node (ref "U$1") (pin "8") (pinfunction "PE22/UART1/RX_8") (pintype "bidirectional"))
      (node (ref "U$8") (pin "9") (pinfunction "SDA_9") (pintype "bidirectional"))
      (node (ref "X3") (pin "18") (pinfunction "S_18") (pintype "passive"))
    )
    (net (code "40") (name "KEYADC0") (class "Default")
      (node (ref "C34") (pin "2") (pinfunction "2_2") (pintype "passive"))
      (node (ref "R20") (pin "2") (pinfunction "2_2") (pintype "passive"))
      (node (ref "R29") (pin "1") (pinfunction "1_1") (pintype "passive"))
      (node (ref "U$1") (pin "112") (pinfunction "LRADC0_112") (pintype "bidirectional"))
    )
    (net (code "41") (name "LCD_D19") (class "Default")
      (node (ref "J3") (pin "8") (pinfunction "MS_8") (pintype "passive"))
      (node (ref "JP12") (pin "14") (pinfunction "14_14") (pintype "passive"))
      (node (ref "U$1") (pin "14") (pinfunction "PE17/CSI-D13/LCD-D19_14") (pintype "bidirectional"))
    )
    (net (code "42") (name "LCD_D20") (class "Default")
      (node (ref "J3") (pin "9") (pinfunction "MS_9") (pintype "passive"))
      (node (ref "JP12") (pin "13") (pinfunction "13_13") (pintype "passive"))
      (node (ref "U$1") (pin "13") (pinfunction "PE18/CSI-D14/LCD-D20_13") (pintype "bidirectional"))
    )
    (net (code "43") (name "LCD_D21") (class "Default")
      (node (ref "J3") (pin "10") (pinfunction "MS_10") (pintype "passive"))
      (node (ref "JP12") (pin "12") (pinfunction "12_12") (pintype "passive"))
      (node (ref "U$1") (pin "11") (pinfunction "PE19/CSI-D15/LCD-D21_11") (pintype "bidirectional"))
    )
    (net (code "44") (name "LCD_D22") (class "Default")
      (node (ref "J3") (pin "11") (pinfunction "MS_11") (pintype "passive"))
      (node (ref "JP12") (pin "9") (pinfunction "9_9") (pintype "passive"))
      (node (ref "U$1") (pin "7") (pinfunction "PE23/LCD-D22/_7") (pintype "bidirectional"))
    )
    (net (code "45") (name "LCD_D23") (class "Default")
      (node (ref "J3") (pin "12") (pinfunction "MS_12") (pintype "passive"))
      (node (ref "JP12") (pin "8") (pinfunction "8_8") (pintype "passive"))
      (node (ref "U$1") (pin "6") (pinfunction "PE24/LCD-D23_6") (pintype "bidirectional"))
    )
    (net (code "46") (name "LINK_LED") (class "Default")
      (node (ref "R53") (pin "1") (pinfunction "1_1") (pintype "passive"))
      (node (ref "U$1") (pin "77") (pinfunction "EPHY_LINK_LED_77") (pintype "bidirectional"))
    )
    (net (code "47") (name "MCSI-CKN") (class "Default")
      (node (ref "J4") (pin "8") (pinfunction "8_8") (pintype "passive"))
      (node (ref "U$1") (pin "87") (pinfunction "MCSI-CKN_87") (pintype "bidirectional"))
    )
    (net (code "48") (name "MCSI-CKP") (class "Default")
      (node (ref "J4") (pin "7") (pinfunction "9_7") (pintype "passive"))
      (node (ref "U$1") (pin "86") (pinfunction "MCSI-CKP_86") (pintype "bidirectional"))
    )
    (net (code "49") (name "MCSI-D0N") (class "Default")
      (node (ref "J4") (pin "14") (pinfunction "2_14") (pintype "passive"))
      (node (ref "U$1") (pin "82") (pinfunction "MCSI-D0N_82") (pintype "bidirectional"))
    )
    (net (code "50") (name "MCSI-D0P") (class "Default")
      (node (ref "J4") (pin "13") (pinfunction "3_13") (pintype "passive"))
      (node (ref "U$1") (pin "81") (pinfunction "MCSI-D0P_81") (pintype "bidirectional"))
    )
    (net (code "51") (name "MCSI-D1N") (class "Default")
      (node (ref "J4") (pin "11") (pinfunction "5_11") (pintype "passive"))
      (node (ref "U$1") (pin "84") (pinfunction "MCSI-D1N_84") (pintype "bidirectional"))
    )
    (net (code "52") (name "MCSI-D1P") (class "Default")
      (node (ref "J4") (pin "10") (pinfunction "6_10") (pintype "passive"))
      (node (ref "U$1") (pin "83") (pinfunction "MCSI-D1P_83") (pintype "bidirectional"))
    )
    (net (code "53") (name "MICIN1N") (class "Default")
      (node (ref "C28") (pin "1") (pinfunction "1_1") (pintype "passive"))
      (node (ref "U$1") (pin "114") (pinfunction "MICIN1N_114") (pintype "bidirectional"))
    )
    (net (code "54") (name "MICIN1P") (class "Default")
      (node (ref "C27") (pin "1") (pinfunction "1_1") (pintype "passive"))
      (node (ref "U$1") (pin "113") (pinfunction "MICIN1P_113") (pintype "bidirectional"))
    )
    (net (code "55") (name "MIC_HBIAS") (class "Default")
      (node (ref "C17") (pin "1") (pinfunction "1_1") (pintype "passive"))
      (node (ref "R25") (pin "2") (pinfunction "2_2") (pintype "passive"))
      (node (ref "U$1") (pin "119") (pinfunction "HBIAS_119") (pintype "bidirectional"))
    )
    (net (code "56") (name "MIPI-CSI-MCLK") (class "Default")
      (node (ref "J4") (pin "5") (pinfunction "11_5") (pintype "passive"))
      (node (ref "JP1") (pin "15") (pinfunction "15_15") (pintype "passive"))
      (node (ref "U$1") (pin "10") (pinfunction "PE20/CSI-FIELD/CSI-MIPI-M-CLK_10") (pintype "bidirectional"))
    )
    (net (code "57") (name "Net-(ANT1-Pad2)") (class "Default")
      (node (ref "ANT1") (pin "2") (pinfunction "2_2") (pintype "passive"))
      (node (ref "C4") (pin "2") (pinfunction "2_2") (pintype "passive"))
      (node (ref "C6") (pin "1") (pinfunction "1_1") (pintype "passive"))
    )
    (net (code "58") (name "Net-(C18-Pad1)") (class "Default")
      (node (ref "C18") (pin "1") (pinfunction "1_1") (pintype "passive"))
      (node (ref "R15") (pin "2") (pinfunction "2_2") (pintype "passive"))
    )
    (net (code "59") (name "Net-(C23-Pad2)") (class "Default")
      (node (ref "C23") (pin "2") (pinfunction "2_2") (pintype "passive"))
      (node (ref "C25") (pin "2") (pinfunction "2_2") (pintype "passive"))
      (node (ref "C27") (pin "2") (pinfunction "2_2") (pintype "passive"))
      (node (ref "MIC") (pin "2") (pinfunction "2_2") (pintype "passive"))
      (node (ref "R30") (pin "1") (pinfunction "1_1") (pintype "passive"))
    )
    (net (code "60") (name "Net-(C24-Pad2)") (class "Default")
      (node (ref "C24") (pin "2") (pinfunction "2_2") (pintype "passive"))
      (node (ref "C25") (pin "1") (pinfunction "1_1") (pintype "passive"))
      (node (ref "C28") (pin "2") (pinfunction "2_2") (pintype "passive"))
      (node (ref "MIC") (pin "1") (pinfunction "1_1") (pintype "passive"))
      (node (ref "R28") (pin "1") (pinfunction "1_1") (pintype "passive"))
    )
    (net (code "61") (name "Net-(CN2-PadPWR)") (class "Default")
      (node (ref "CN2") (pin "PWR") (pinfunction "PWR_PWR") (pintype "power_in"))
      (node (ref "F1") (pin "1") (pinfunction "1_1") (pintype "passive"))
    )
    (net (code "62") (name "Net-(J2-PadEARTH)") (class "Default")
      (node (ref "J2") (pin "EARTH") (pinfunction "EARTH_EARTH") (pintype "bidirectional"))
      (node (ref "R25") (pin "1") (pinfunction "1_1") (pintype "passive"))
    )
    (net (code "63") (name "Net-(L1-2)") (class "Default")
      (node (ref "D1") (pin "A") (pinfunction "A_A") (pintype "passive"))
      (node (ref "L1") (pin "P$2") (pinfunction "2_P$2") (pintype "passive"))
      (node (ref "U$9") (pin "1") (pinfunction "SW_1") (pintype "bidirectional"))
    )
    (net (code "64") (name "Net-(L3-2)") (class "Default")
      (node (ref "L3") (pin "P$2") (pinfunction "2_P$2") (pintype "passive"))
      (node (ref "U$4") (pin "11") (pinfunction "LX1_11") (pintype "bidirectional"))
    )
    (net (code "65") (name "Net-(L4-2)") (class "Default")
      (node (ref "L4") (pin "P$2") (pinfunction "2_P$2") (pintype "passive"))
      (node (ref "U$4") (pin "6") (pinfunction "LX2_6") (pintype "bidirectional"))
    )
    (net (code "66") (name "Net-(L5-2)") (class "Default")
      (node (ref "L5") (pin "P$2") (pinfunction "2_P$2") (pintype "passive"))
      (node (ref "U$4") (pin "20") (pinfunction "LX3_20") (pintype "bidirectional"))
    )
    (net (code "67") (name "Net-(LED1-PadA)") (class "Default")
      (node (ref "LED1") (pin "A") (pinfunction "A_A") (pintype "passive"))
      (node (ref "R16") (pin "1") (pinfunction "1_1") (pintype "passive"))
    )
    (net (code "68") (name "Net-(LED2-PadA)") (class "Default")
      (node (ref "LED2") (pin "A") (pinfunction "A_A") (pintype "passive"))
      (node (ref "R17") (pin "1") (pinfunction "1_1") (pintype "passive"))
    )
    (net (code "69") (name "Net-(R20-Pad1)") (class "Default")
      (node (ref "R20") (pin "1") (pinfunction "1_1") (pintype "passive"))
      (node (ref "R21") (pin "2") (pinfunction "2_2") (pintype "passive"))
      (node (ref "S1") (pin "2") (pinfunction "2_2") (pintype "passive"))
    )
    (net (code "70") (name "Net-(R21-Pad1)") (class "Default")
      (node (ref "R21") (pin "1") (pinfunction "1_1") (pintype "passive"))
      (node (ref "R22") (pin "2") (pinfunction "2_2") (pintype "passive"))
      (node (ref "S2") (pin "2") (pinfunction "2_2") (pintype "passive"))
    )
    (net (code "71") (name "Net-(R22-Pad1)") (class "Default")
      (node (ref "R22") (pin "1") (pinfunction "1_1") (pintype "passive"))
      (node (ref "R23") (pin "2") (pinfunction "2_2") (pintype "passive"))
      (node (ref "S3") (pin "2") (pinfunction "2_2") (pintype "passive"))
    )
    (net (code "72") (name "Net-(R23-Pad1)") (class "Default")
      (node (ref "R23") (pin "1") (pinfunction "1_1") (pintype "passive"))
      (node (ref "S4") (pin "2") (pinfunction "2_2") (pintype "passive"))
    )
    (net (code "73") (name "Net-(U$1A-HPVCCBP)") (class "Default")
      (node (ref "C22") (pin "1") (pinfunction "1_1") (pintype "passive"))
      (node (ref "C29") (pin "2") (pinfunction "2_2") (pintype "passive"))
      (node (ref "U$1") (pin "123") (pinfunction "HPVCCBP_123") (pintype "bidirectional"))
    )
    (net (code "74") (name "Net-(U$1D-RESET)") (class "Default")
      (node (ref "C13") (pin "1") (pinfunction "1_1") (pintype "passive"))
      (node (ref "R11") (pin "1") (pinfunction "1_1") (pintype "passive"))
      (node (ref "S5") (pin "2") (pinfunction "2_2") (pintype "passive"))
      (node (ref "U$1") (pin "99") (pinfunction "RESET_99") (pintype "bidirectional"))
    )
    (net (code "75") (name "Net-(U$1D-X24MIN)") (class "Default")
      (node (ref "C12") (pin "2") (pinfunction "2_2") (pintype "passive"))
      (node (ref "Q1") (pin "2") (pinfunction "2_2") (pintype "passive"))
      (node (ref "U$1") (pin "75") (pinfunction "X24MIN_75") (pintype "bidirectional"))
    )
    (net (code "76") (name "Net-(U$1D-X24MOUNT)") (class "Default")
      (node (ref "C11") (pin "2") (pinfunction "2_2") (pintype "passive"))
      (node (ref "Q1") (pin "1") (pinfunction "1_1") (pintype "passive"))
      (node (ref "U$1") (pin "74") (pinfunction "X24MOUNT_74") (pintype "bidirectional"))
    )
    (net (code "77") (name "Net-(U$1D-X32KIN)") (class "Default")
      (node (ref "C8") (pin "1") (pinfunction "1_1") (pintype "passive"))
      (node (ref "Q2") (pin "1") (pinfunction "1_1") (pintype "passive"))
      (node (ref "U$1") (pin "96") (pinfunction "X32KIN_96") (pintype "bidirectional"))
    )
    (net (code "78") (name "Net-(U$1D-X32KOUT)") (class "Default")
      (node (ref "C10") (pin "1") (pinfunction "1_1") (pintype "passive"))
      (node (ref "Q2") (pin "2") (pinfunction "2_2") (pintype "passive"))
      (node (ref "U$1") (pin "95") (pinfunction "X32KOUT_95") (pintype "bidirectional"))
    )
    (net (code "79") (name "Net-(U$1E-EPHY_RTX)") (class "Default")
      (node (ref "R24") (pin "1") (pinfunction "1_1") (pintype "passive"))
      (node (ref "U$1") (pin "94") (pinfunction "EPHY_RTX_94") (pintype "bidirectional"))
    )
    (net (code "80") (name "Net-(U$1F-RTC-VIO)") (class "Default")
      (node (ref "C7") (pin "1") (pinfunction "1_1") (pintype "passive"))
      (node (ref "U$1") (pin "97") (pinfunction "RTC-VIO_97") (pintype "bidirectional"))
    )
    (net (code "81") (name "Net-(U$1F-VCC-RTC)") (class "Default")
      (node (ref "JP5") (pin "2") (pinfunction "2_2") (pintype "passive"))
      (node (ref "U$1") (pin "98") (pinfunction "VCC-RTC_98") (pintype "bidirectional"))
    )
    (net (code "82") (name "Net-(U$1G-SZQ)") (class "Default")
      (node (ref "R12") (pin "1") (pinfunction "1_1") (pintype "passive"))
      (node (ref "U$1") (pin "73") (pinfunction "SZQ_73") (pintype "bidirectional"))
    )
    (net (code "83") (name "Net-(U$2-BT_RST)") (class "Default")
      (node (ref "R10") (pin "1") (pinfunction "1_1") (pintype "passive"))
      (node (ref "U$2") (pin "P$34") (pinfunction "BT_RST_P$34") (pintype "bidirectional"))
    )
    (net (code "84") (name "Net-(U$2-UART_CTS)") (class "Default")
      (node (ref "JP7") (pin "1") (pinfunction "1_1") (pintype "passive"))
      (node (ref "U$2") (pin "P$44") (pinfunction "UART_CTS_P$44") (pintype "bidirectional"))
    )
    (net (code "85") (name "Net-(U$2-UART_RXD)") (class "Default")
      (node (ref "JP7") (pin "2") (pinfunction "2_2") (pintype "passive"))
      (node (ref "U$2") (pin "P$43") (pinfunction "UART_RXD_P$43") (pintype "bidirectional"))
    )
    (net (code "86") (name "Net-(U$2-UART_TXD)") (class "Default")
      (node (ref "JP7") (pin "3") (pinfunction "3_3") (pintype "passive"))
      (node (ref "U$2") (pin "P$42") (pinfunction "UART_TXD_P$42") (pintype "bidirectional"))
    )
    (net (code "87") (name "Net-(U$2-VIN_LDO)") (class "Default")
      (node (ref "R19") (pin "1") (pinfunction "1_1") (pintype "passive"))
      (node (ref "U$2") (pin "P$23") (pinfunction "VIN_LDO_P$23") (pintype "bidirectional"))
    )
    (net (code "88") (name "Net-(U$2-WL_BT_ANT)") (class "Default")
      (node (ref "C4") (pin "1") (pinfunction "1_1") (pintype "passive"))
      (node (ref "C5") (pin "1") (pinfunction "1_1") (pintype "passive"))
      (node (ref "U$2") (pin "P$2") (pinfunction "WL_BT_ANT_P$2") (pintype "bidirectional"))
    )
    (net (code "89") (name "Net-(U$2-WL_REG)") (class "Default")
      (node (ref "R9") (pin "2") (pinfunction "2_2") (pintype "passive"))
      (node (ref "U$2") (pin "P$12") (pinfunction "WL_REG_P$12") (pintype "bidirectional"))
    )
    (net (code "90") (name "Net-(U$3-G+)") (class "Default")
      (node (ref "R53") (pin "2") (pinfunction "2_2") (pintype "passive"))
      (node (ref "U$3") (pin "9") (pinfunction "G+_9") (pintype "bidirectional"))
    )
    (net (code "91") (name "Net-(U$3-P4)") (class "Default")
      (node (ref "C49") (pin "1") (pinfunction "1_1") (pintype "passive"))
      (node (ref "L2") (pin "2") (pinfunction "2_2") (pintype "passive"))
      (node (ref "R42") (pin "2") (pinfunction "2_2") (pintype "passive"))
      (node (ref "R43") (pin "2") (pinfunction "2_2") (pintype "passive"))
      (node (ref "U$3") (pin "4") (pinfunction "P4_4") (pintype "bidirectional"))
    )
    (net (code "92") (name "Net-(U$3-P5)") (class "Default")
      (node (ref "C48") (pin "1") (pinfunction "1_1") (pintype "passive"))
      (node (ref "R40") (pin "2") (pinfunction "2_2") (pintype "passive"))
      (node (ref "R41") (pin "2") (pinfunction "2_2") (pintype "passive"))
      (node (ref "U$3") (pin "5") (pinfunction "P5_5") (pintype "bidirectional"))
    )
    (net (code "93") (name "Net-(U$3-Y+)") (class "Default")
      (node (ref "R52") (pin "2") (pinfunction "2_2") (pintype "passive"))
      (node (ref "U$3") (pin "12") (pinfunction "Y+_12") (pintype "bidirectional"))
    )
    (net (code "94") (name "Net-(U$4-FB1)") (class "Default")
      (node (ref "C41") (pin "2") (pinfunction "2_2") (pintype "passive"))
      (node (ref "R54") (pin "2") (pinfunction "2_2") (pintype "passive"))
      (node (ref "R7") (pin "2") (pinfunction "2_2") (pintype "passive"))
      (node (ref "U$4") (pin "14") (pinfunction "FB1_14") (pintype "bidirectional"))
    )
    (net (code "95") (name "Net-(U$4-FB2)") (class "Default")
      (node (ref "C42") (pin "2") (pinfunction "2_2") (pintype "passive"))
      (node (ref "R55") (pin "2") (pinfunction "2_2") (pintype "passive"))
      (node (ref "R56") (pin "2") (pinfunction "2_2") (pintype "passive"))
      (node (ref "U$4") (pin "3") (pinfunction "FB2_3") (pintype "bidirectional"))
    )
    (net (code "96") (name "Net-(U$4-FB3)") (class "Default")
      (node (ref "C45") (pin "2") (pinfunction "2_2") (pintype "passive"))
      (node (ref "R57") (pin "2") (pinfunction "2_2") (pintype "passive"))
      (node (ref "R58") (pin "2") (pinfunction "2_2") (pintype "passive"))
      (node (ref "U$4") (pin "2") (pinfunction "FB3_2") (pintype "bidirectional"))
    )
    (net (code "97") (name "Net-(U$7-D)") (class "Default")
      (node (ref "F1") (pin "2") (pinfunction "2_2") (pintype "passive"))
      (node (ref "U$7") (pin "3") (pinfunction "D_3") (pintype "passive"))
    )
    (net (code "98") (name "Net-(U$9-EN)") (class "Default")
      (node (ref "R46") (pin "1") (pinfunction "1_1") (pintype "passive"))
      (node (ref "U$9") (pin "4") (pinfunction "EN_4") (pintype "bidirectional"))
    )
    (net (code "99") (name "PB2") (class "Default")
      (node (ref "JP1") (pin "12") (pinfunction "12_12") (pintype "passive"))
      (node (ref "R17") (pin "2") (pinfunction "2_2") (pintype "passive"))
      (node (ref "U$1") (pin "41") (pinfunction "PB2_41") (pintype "bidirectional"))
    )
    (net (code "100") (name "PB3") (class "Default")
      (node (ref "J4") (pin "4") (pinfunction "12_4") (pintype "passive"))
      (node (ref "JP1") (pin "7") (pinfunction "7_7") (pintype "passive"))
      (node (ref "U$1") (pin "42") (pinfunction "PB3_42") (pintype "bidirectional"))
    )
    (net (code "101") (name "PB4{slash}PWM0") (class "Default")
      (node (ref "JP1") (pin "13") (pinfunction "13_13") (pintype "passive"))
      (node (ref "U$1") (pin "43") (pinfunction "PB4/PWM0_43") (pintype "bidirectional"))
    )
    (net (code "102") (name "PB5{slash}PWM1") (class "Default")
      (node (ref "JP1") (pin "11") (pinfunction "11_11") (pintype "passive"))
      (node (ref "U$1") (pin "44") (pinfunction "PB5/PWM1_44") (pintype "bidirectional"))
    )
    (net (code "103") (name "SDC0{slash}CLK") (class "Default")
      (node (ref "J1") (pin "5") (pinfunction "CLK(SCLK)_5") (pintype "bidirectional"))
      (node (ref "RN2") (pin "5") (pinfunction "2_5") (pintype "passive"))
      (node (ref "U$1") (pin "105") (pinfunction "PF2/SDC0/CLK_105") (pintype "bidirectional"))
    )
    (net (code "104") (name "SDC0{slash}CMD") (class "Default")
      (node (ref "J1") (pin "3") (pinfunction "CMD(DI)_3") (pintype "bidirectional"))
      (node (ref "RN2") (pin "6") (pinfunction "2_6") (pintype "passive"))
      (node (ref "U$1") (pin "103") (pinfunction "PF3/SDC0/CMD_103") (pintype "bidirectional"))
    )
    (net (code "105") (name "SDC0{slash}D0") (class "Default")
      (node (ref "J1") (pin "7") (pinfunction "DAT0(DO)_7") (pintype "bidirectional"))
      (node (ref "R1") (pin "1") (pinfunction "1_1") (pintype "passive"))
      (node (ref "U$1") (pin "106") (pinfunction "PF1/SDC0/D0_106") (pintype "bidirectional"))
    )
    (net (code "106") (name "SDC0{slash}D1") (class "Default")
      (node (ref "J1") (pin "8") (pinfunction "DAT1_8") (pintype "bidirectional"))
      (node (ref "R2") (pin "1") (pinfunction "1_1") (pintype "passive"))
      (node (ref "U$1") (pin "107") (pinfunction "PF0/SDC0/D1_107") (pintype "bidirectional"))
    )
    (net (code "107") (name "SDC0{slash}D2") (class "Default")
      (node (ref "J1") (pin "1") (pinfunction "DAT2_1") (pintype "bidirectional"))
      (node (ref "RN2") (pin "8") (pinfunction "2_8") (pintype "passive"))
      (node (ref "U$1") (pin "101") (pinfunction "PF5/SDC0/D2_101") (pintype "bidirectional"))
    )
    (net (code "108") (name "SDC0{slash}D3") (class "Default")
      (node (ref "J1") (pin "2") (pinfunction "CD/DAT3(~{CS})_2") (pintype "bidirectional"))
      (node (ref "RN2") (pin "7") (pinfunction "2_7") (pintype "passive"))
      (node (ref "U$1") (pin "102") (pinfunction "PF4/SDC0/D3_102") (pintype "bidirectional"))
    )
    (net (code "109") (name "SDC1{slash}CLK") (class "Default")
      (node (ref "JP2") (pin "3") (pinfunction "3_3") (pintype "passive"))
      (node (ref "U$1") (pin "5") (pinfunction "PG0/SDC1/CLK_5") (pintype "bidirectional"))
      (node (ref "U$2") (pin "P$17") (pinfunction "SDIO_CLK_P$17") (pintype "bidirectional"))
    )
    (net (code "110") (name "SDC1{slash}CMD") (class "Default")
      (node (ref "JP2") (pin "4") (pinfunction "4_4") (pintype "passive"))
      (node (ref "R36") (pin "2") (pinfunction "2_2") (pintype "passive"))
      (node (ref "U$1") (pin "4") (pinfunction "PG1/SDC1/CMD_4") (pintype "bidirectional"))
      (node (ref "U$2") (pin "P$16") (pinfunction "SDIO_CMD_P$16") (pintype "bidirectional"))
    )
    (net (code "111") (name "SDC1{slash}D0") (class "Default")
      (node (ref "JP2") (pin "2") (pinfunction "2_2") (pintype "passive"))
      (node (ref "RN1") (pin "5") (pinfunction "2_5") (pintype "passive"))
      (node (ref "U$1") (pin "3") (pinfunction "PG2/SDC1/D0_3") (pintype "bidirectional"))
      (node (ref "U$2") (pin "P$18") (pinfunction "SDIO_D0_P$18") (pintype "bidirectional"))
    )
    (net (code "112") (name "SDC1{slash}D1") (class "Default")
      (node (ref "JP2") (pin "1") (pinfunction "1_1") (pintype "passive"))
      (node (ref "RN1") (pin "6") (pinfunction "2_6") (pintype "passive"))
      (node (ref "U$1") (pin "2") (pinfunction "PG3/SDC1/D1_2") (pintype "bidirectional"))
      (node (ref "U$2") (pin "P$19") (pinfunction "SDIO_D1_P$19") (pintype "bidirectional"))
    )
    (net (code "113") (name "SDC1{slash}D2") (class "Default")
      (node (ref "JP2") (pin "6") (pinfunction "6_6") (pintype "passive"))
      (node (ref "RN1") (pin "7") (pinfunction "2_7") (pintype "passive"))
      (node (ref "U$1") (pin "1") (pinfunction "PG4/SDC1/D2_1") (pintype "bidirectional"))
      (node (ref "U$2") (pin "P$14") (pinfunction "SDIO_D2_P$14") (pintype "bidirectional"))
    )
    (net (code "114") (name "SDC1{slash}D3") (class "Default")
      (node (ref "JP2") (pin "5") (pinfunction "5_5") (pintype "passive"))
      (node (ref "RN1") (pin "8") (pinfunction "2_8") (pintype "passive"))
      (node (ref "U$1") (pin "128") (pinfunction "PG5/SDC1/D3_128") (pintype "bidirectional"))
      (node (ref "U$2") (pin "P$15") (pinfunction "SDIO_D3_P$15") (pintype "bidirectional"))
    )
    (net (code "115") (name "SPD_LED") (class "Default")
      (node (ref "R52") (pin "1") (pinfunction "1_1") (pintype "passive"))
      (node (ref "U$1") (pin "78") (pinfunction "EPHY_SPD_LED_78") (pintype "bidirectional"))
    )
    (net (code "116") (name "SPI1{slash}CS") (class "Default")
      (node (ref "IC3") (pin "4") (pinfunction "CS_4") (pintype "bidirectional"))
      (node (ref "JP1") (pin "24") (pinfunction "24_24") (pintype "passive"))
      (node (ref "R8") (pin "2") (pinfunction "2_2") (pintype "passive"))
      (node (ref "U$1") (pin "54") (pinfunction "PC2/SPI1/CS_54") (pintype "bidirectional"))
    )
    (net (code "117") (name "SPI1{slash}MISO") (class "Default")
      (node (ref "IC3") (pin "8") (pinfunction "SO_8") (pintype "bidirectional"))
      (node (ref "JP1") (pin "21") (pinfunction "21_21") (pintype "passive"))
      (node (ref "U$1") (pin "52") (pinfunction "PC0/SPI1/MISO_52") (pintype "bidirectional"))
    )
    (net (code "118") (name "SPI1{slash}MOSI") (class "Default")
      (node (ref "IC3") (pin "1") (pinfunction "SI_1") (pintype "bidirectional"))
      (node (ref "JP1") (pin "19") (pinfunction "19_19") (pintype "passive"))
      (node (ref "U$1") (pin "55") (pinfunction "PC3/SPI1/MOSI_55") (pintype "bidirectional"))
    )
    (net (code "119") (name "SPI1{slash}SCK") (class "Default")
      (node (ref "IC3") (pin "2") (pinfunction "SCK_2") (pintype "bidirectional"))
      (node (ref "JP1") (pin "23") (pinfunction "23_23") (pintype "passive"))
      (node (ref "U$1") (pin "53") (pinfunction "PC1/SPI1/SCK_53") (pintype "bidirectional"))
    )
    (net (code "120") (name "SVREF") (class "Default")
      (node (ref "C14") (pin "1") (pinfunction "1_1") (pintype "passive"))
      (node (ref "C15") (pin "2") (pinfunction "2_2") (pintype "passive"))
      (node (ref "R13") (pin "1") (pinfunction "1_1") (pintype "passive"))
      (node (ref "R14") (pin "2") (pinfunction "2_2") (pintype "passive"))
      (node (ref "U$1") (pin "63") (pinfunction "SVREF1_63") (pintype "bidirectional"))
      (node (ref "U$1") (pin "71") (pinfunction "SVREF0_71") (pintype "bidirectional"))
    )
    (net (code "121") (name "TPX1") (class "Default")
      (node (ref "J3") (pin "37") (pinfunction "MS_37") (pintype "passive"))
      (node (ref "U$8") (pin "2") (pinfunction "XP_2") (pintype "bidirectional"))
    )
    (net (code "122") (name "TPX2") (class "Default")
      (node (ref "J3") (pin "39") (pinfunction "MS_39") (pintype "passive"))
      (node (ref "U$8") (pin "4") (pinfunction "XN_4") (pintype "bidirectional"))
    )
    (net (code "123") (name "TPY1") (class "Default")
      (node (ref "J3") (pin "38") (pinfunction "MS_38") (pintype "passive"))
      (node (ref "U$8") (pin "3") (pinfunction "YP_3") (pintype "bidirectional"))
    )
    (net (code "124") (name "TPY2") (class "Default")
      (node (ref "J3") (pin "40") (pinfunction "MS_40") (pintype "passive"))
      (node (ref "U$8") (pin "5") (pinfunction "YN_5") (pintype "bidirectional"))
    )
    (net (code "125") (name "UART0{slash}RX") (class "Default")
      (node (ref "JP1") (pin "10") (pinfunction "10_10") (pintype "passive"))
      (node (ref "U$1") (pin "49") (pinfunction "PB9/I2C1/SDA_49") (pintype "bidirectional"))
    )
    (net (code "126") (name "UART0{slash}TX") (class "Default")
      (node (ref "JP1") (pin "8") (pinfunction "8_8") (pintype "passive"))
      (node (ref "U$1") (pin "48") (pinfunction "PB8/I2C1/SCL_48") (pintype "bidirectional"))
    )
    (net (code "127") (name "UART2{slash}RX{slash}PB1") (class "Default")
      (node (ref "JP1") (pin "16") (pinfunction "16_16") (pintype "passive"))
      (node (ref "U$1") (pin "40") (pinfunction "PB1/UART2/RX_40") (pintype "bidirectional"))
    )
    (net (code "128") (name "UART2{slash}TX{slash}PB0") (class "Default")
      (node (ref "JP1") (pin "18") (pinfunction "18_18") (pintype "passive"))
      (node (ref "U$1") (pin "39") (pinfunction "PB0/UART2/TX_39") (pintype "bidirectional"))
    )
    (net (code "129") (name "USB_DM") (class "Default")
      (node (ref "U$1") (pin "110") (pinfunction "USB-DM_110") (pintype "bidirectional"))
      (node (ref "U$5") (pin "2") (pinfunction "2_2") (pintype "input"))
      (node (ref "X1") (pin "D-") (pinfunction "D-_D-") (pintype "bidirectional"))
    )
    (net (code "130") (name "USB_DP") (class "Default")
      (node (ref "U$1") (pin "111") (pinfunction "USB-DP_111") (pintype "bidirectional"))
      (node (ref "U$5") (pin "3") (pinfunction "3_3") (pintype "input"))
      (node (ref "X1") (pin "D+") (pinfunction "D+_D+") (pintype "bidirectional"))
    )
    (net (code "131") (name "USB{slash}ID") (class "Default")
      (node (ref "R32") (pin "2") (pinfunction "2_2") (pintype "passive"))
      (node (ref "U$1") (pin "100") (pinfunction "PF6_100") (pintype "bidirectional"))
      (node (ref "U$5") (pin "4") (pinfunction "4_4") (pintype "input"))
    )
    (net (code "132") (name "VCC-PE") (class "Default")
      (node (ref "JP3") (pin "2") (pinfunction "2_2") (pintype "passive"))
      (node (ref "R44") (pin "1") (pinfunction "1_1") (pintype "passive"))
      (node (ref "R45") (pin "1") (pinfunction "1_1") (pintype "passive"))
      (node (ref "U$1") (pin "12") (pinfunction "VCC-PE0_12") (pintype "bidirectional"))
      (node (ref "U$1") (pin "29") (pinfunction "VCC-PE1_29") (pintype "bidirectional"))
    )
    (net (code "133") (name "VLED+") (class "Default")
      (node (ref "C74") (pin "1") (pinfunction "1_1") (pintype "passive"))
      (node (ref "C75") (pin "1") (pinfunction "1_1") (pintype "passive"))
      (node (ref "D1") (pin "C") (pinfunction "C_C") (pintype "passive"))
      (node (ref "J3") (pin "2") (pinfunction "MS_2") (pintype "passive"))
      (node (ref "U$9") (pin "5") (pinfunction "OV_5") (pintype "bidirectional"))
    )
    (net (code "134") (name "VLED-") (class "Default")
      (node (ref "J3") (pin "1") (pinfunction "MSV_1") (pintype "passive"))
      (node (ref "R47") (pin "1") (pinfunction "1_1") (pintype "passive"))
      (node (ref "U$9") (pin "3") (pinfunction "FB_3") (pintype "bidirectional"))
    )
    (net (code "135") (name "VRA1") (class "Default")
      (node (ref "C21") (pin "2") (pinfunction "2_2") (pintype "passive"))
      (node (ref "U$1") (pin "117") (pinfunction "VRA1_117") (pintype "bidirectional"))
    )
    (net (code "136") (name "VRA2") (class "Default")
      (node (ref "C20") (pin "2") (pinfunction "2_2") (pintype "passive"))
      (node (ref "R27") (pin "2") (pinfunction "2_2") (pintype "passive"))
      (node (ref "U$1") (pin "118") (pinfunction "VRA2_118") (pintype "bidirectional"))
    )
    (net (code "137") (name "WL_H_WK") (class "Default")
      (node (ref "U$2") (pin "P$13") (pinfunction "WL_H_WK_P$13") (pintype "bidirectional"))
    )
    (net (code "138") (name "unconnected-(J3AC-MS-Pad35)") (class "Default")
      (node (ref "J3") (pin "35") (pinfunction "MS_35") (pintype "passive"))
    )
    (net (code "139") (name "unconnected-(U$2-BTXTALOUT-PadP$38)") (class "Default")
      (node (ref "U$2") (pin "P$38") (pinfunction "BTXTALOUT_P$38") (pintype "bidirectional"))
    )
    (net (code "140") (name "unconnected-(U$2-BT_XTAL_IN-PadP$37)") (class "Default")
      (node (ref "U$2") (pin "P$37") (pinfunction "BT_XTAL_IN_P$37") (pintype "bidirectional"))
    )
    (net (code "141") (name "unconnected-(U$2-LPO-PadP$24)") (class "Default")
      (node (ref "U$2") (pin "P$24") (pinfunction "LPO_P$24") (pintype "bidirectional"))
    )
    (net (code "142") (name "unconnected-(U$2-NC4-PadP$4)") (class "Default")
      (node (ref "U$2") (pin "P$4") (pinfunction "NC4_P$4") (pintype "bidirectional"))
    )
    (net (code "143") (name "unconnected-(U$2-NC5-PadP$5)") (class "Default")
      (node (ref "U$2") (pin "P$5") (pinfunction "NC5_P$5") (pintype "bidirectional"))
    )
    (net (code "144") (name "unconnected-(U$2-NC8-PadP$8)") (class "Default")
      (node (ref "U$2") (pin "P$8") (pinfunction "NC8_P$8") (pintype "bidirectional"))
    )
    (net (code "145") (name "unconnected-(U$2-NC32-PadP$32)") (class "Default")
      (node (ref "U$2") (pin "P$32") (pinfunction "NC32_P$32") (pintype "bidirectional"))
    )
    (net (code "146") (name "unconnected-(U$2-NC35-PadP$35)") (class "Default")
      (node (ref "U$2") (pin "P$35") (pinfunction "NC35_P$35") (pintype "bidirectional"))
    )
    (net (code "147") (name "unconnected-(U$2-NC39-PadP$39)") (class "Default")
      (node (ref "U$2") (pin "P$39") (pinfunction "NC39_P$39") (pintype "bidirectional"))
    )
    (net (code "148") (name "unconnected-(U$2-NC40-PadP$40)") (class "Default")
      (node (ref "U$2") (pin "P$40") (pinfunction "NC40_P$40") (pintype "bidirectional"))
    )
    (net (code "149") (name "unconnected-(U$2-PCM_CLK-PadP$26)") (class "Default")
      (node (ref "U$2") (pin "P$26") (pinfunction "PCM_CLK_P$26") (pintype "bidirectional"))
    )
    (net (code "150") (name "unconnected-(U$2-PCM_IN-PadP$27)") (class "Default")
      (node (ref "U$2") (pin "P$27") (pinfunction "PCM_IN_P$27") (pintype "bidirectional"))
    )
    (net (code "151") (name "unconnected-(U$2-PCM_OUT-PadP$25)") (class "Default")
      (node (ref "U$2") (pin "P$25") (pinfunction "PCM_OUT_P$25") (pintype "bidirectional"))
    )
    (net (code "152") (name "unconnected-(U$2-PCM_SYNC-PadP$28)") (class "Default")
      (node (ref "U$2") (pin "P$28") (pinfunction "PCM_SYNC_P$28") (pintype "bidirectional"))
    )
    (net (code "153") (name "unconnected-(U$2-TCXO_IN-PadP$30)") (class "Default")
      (node (ref "U$2") (pin "P$30") (pinfunction "TCXO_IN_P$30") (pintype "bidirectional"))
    )
    (net (code "154") (name "unconnected-(U$2-VDD_TXCO-PadP$29)") (class "Default")
      (node (ref "U$2") (pin "P$29") (pinfunction "VDD_TXCO_P$29") (pintype "bidirectional"))
    )
    (net (code "155") (name "unconnected-(U$2-VIN_LDO_OUT-PadP$21)") (class "Default")
      (node (ref "U$2") (pin "P$21") (pinfunction "VIN_LDO_OUT_P$21") (pintype "bidirectional"))
    )
    (net (code "156") (name "unconnected-(U$2-XTAL_WL_IN-PadP$10)") (class "Default")
      (node (ref "U$2") (pin "P$10") (pinfunction "XTAL_WL_IN_P$10") (pintype "bidirectional"))
    )
    (net (code "157") (name "unconnected-(U$2-XTAL_WL_OUT-PadP$11)") (class "Default")
      (node (ref "U$2") (pin "P$11") (pinfunction "XTAL_WL_OUT_P$11") (pintype "bidirectional"))
    )
    (net (code "158") (name "unconnected-(U$3-NC-Pad7)") (class "Default")
      (node (ref "U$3") (pin "7") (pinfunction "NC_7") (pintype "bidirectional"))
    )
    (net (code "159") (name "unconnected-(U$8-PENIRQ-Pad7)") (class "Default")
      (node (ref "U$8") (pin "7") (pinfunction "PENIRQ_7") (pintype "bidirectional"))
    )
  )
)
